# lipo-charger-station.net
KiCad netlist of a schematic drawn in EAGLE
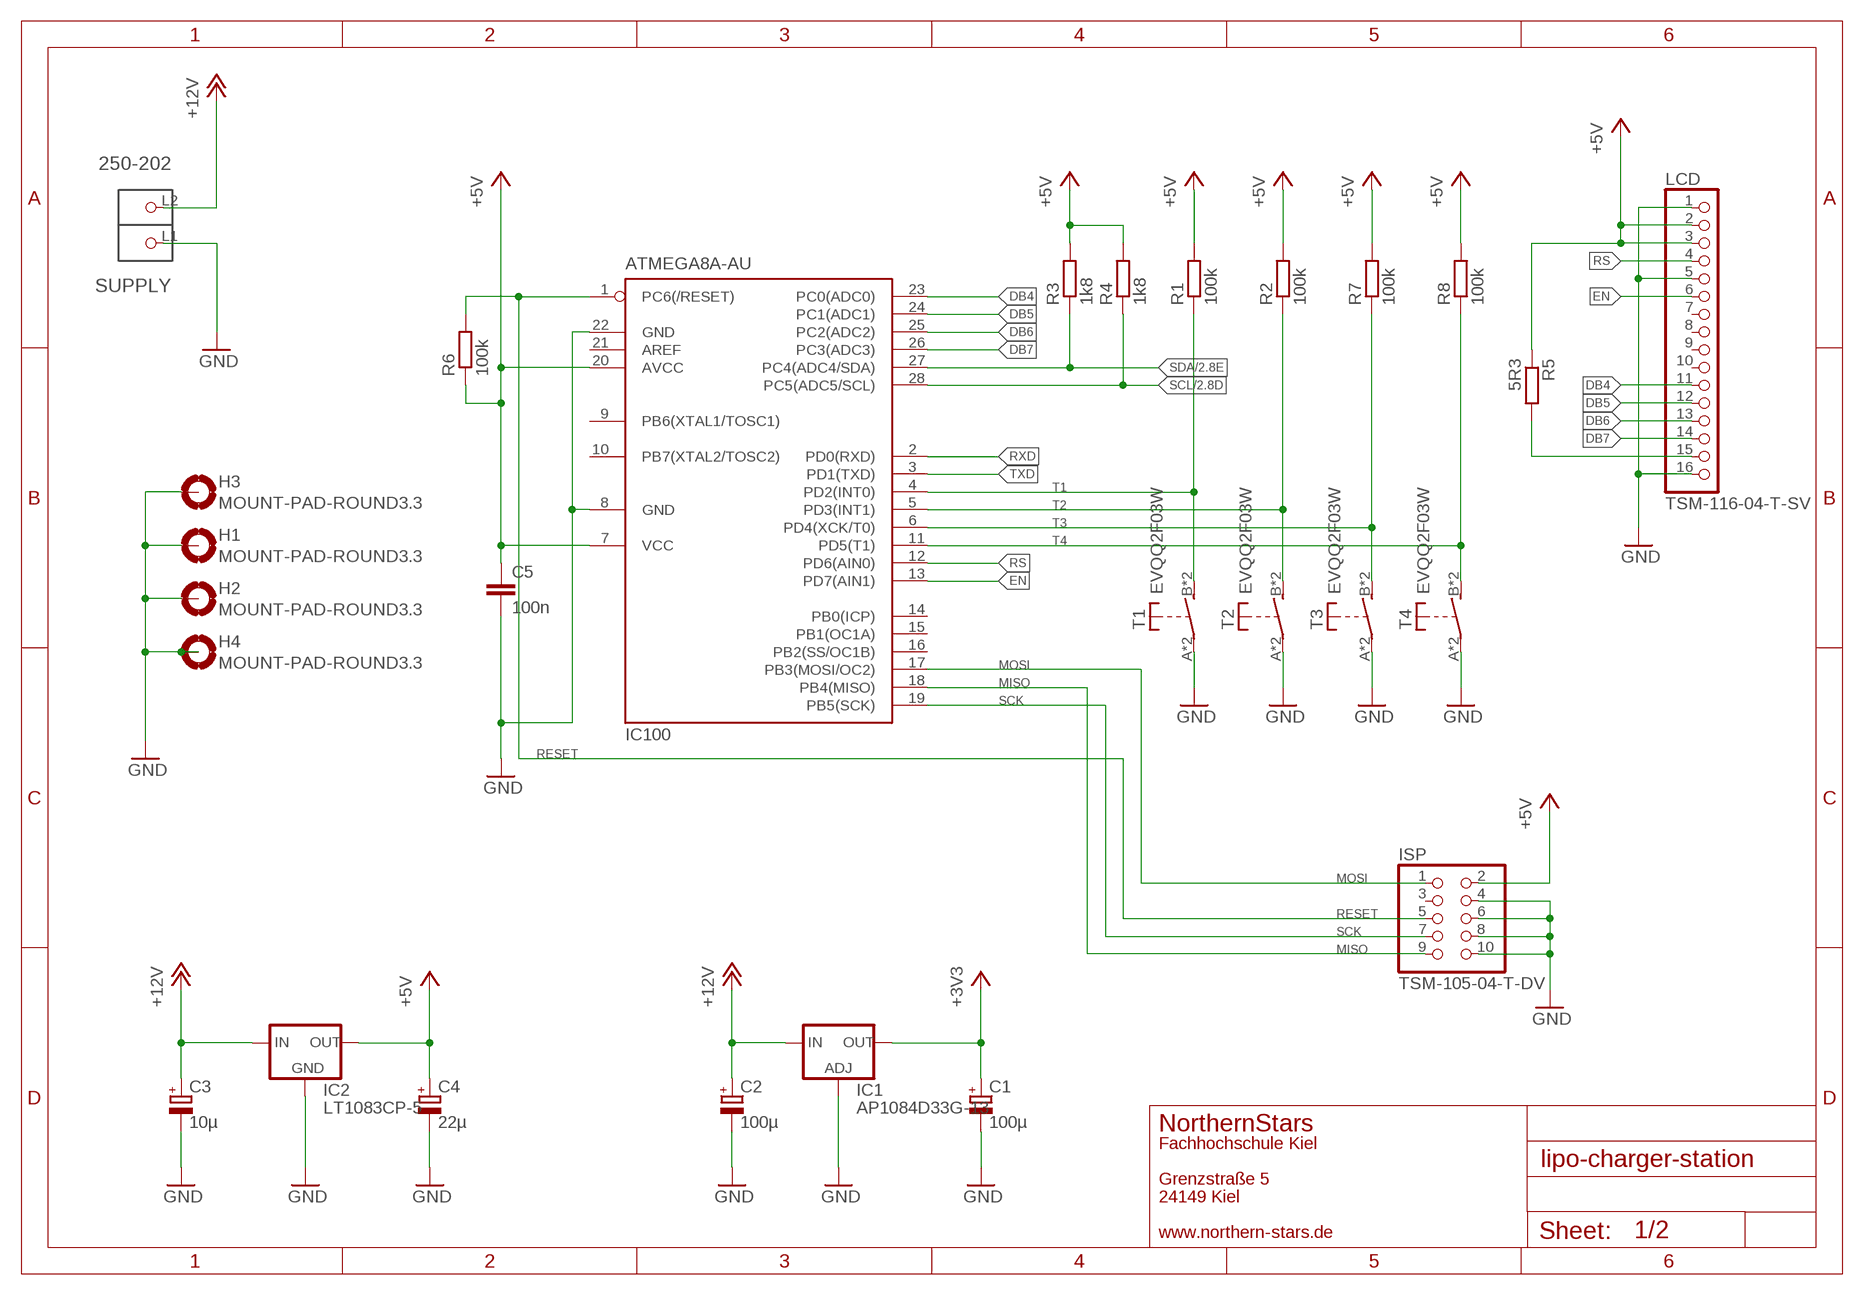
[diagram p0: schematic, sheet 1]
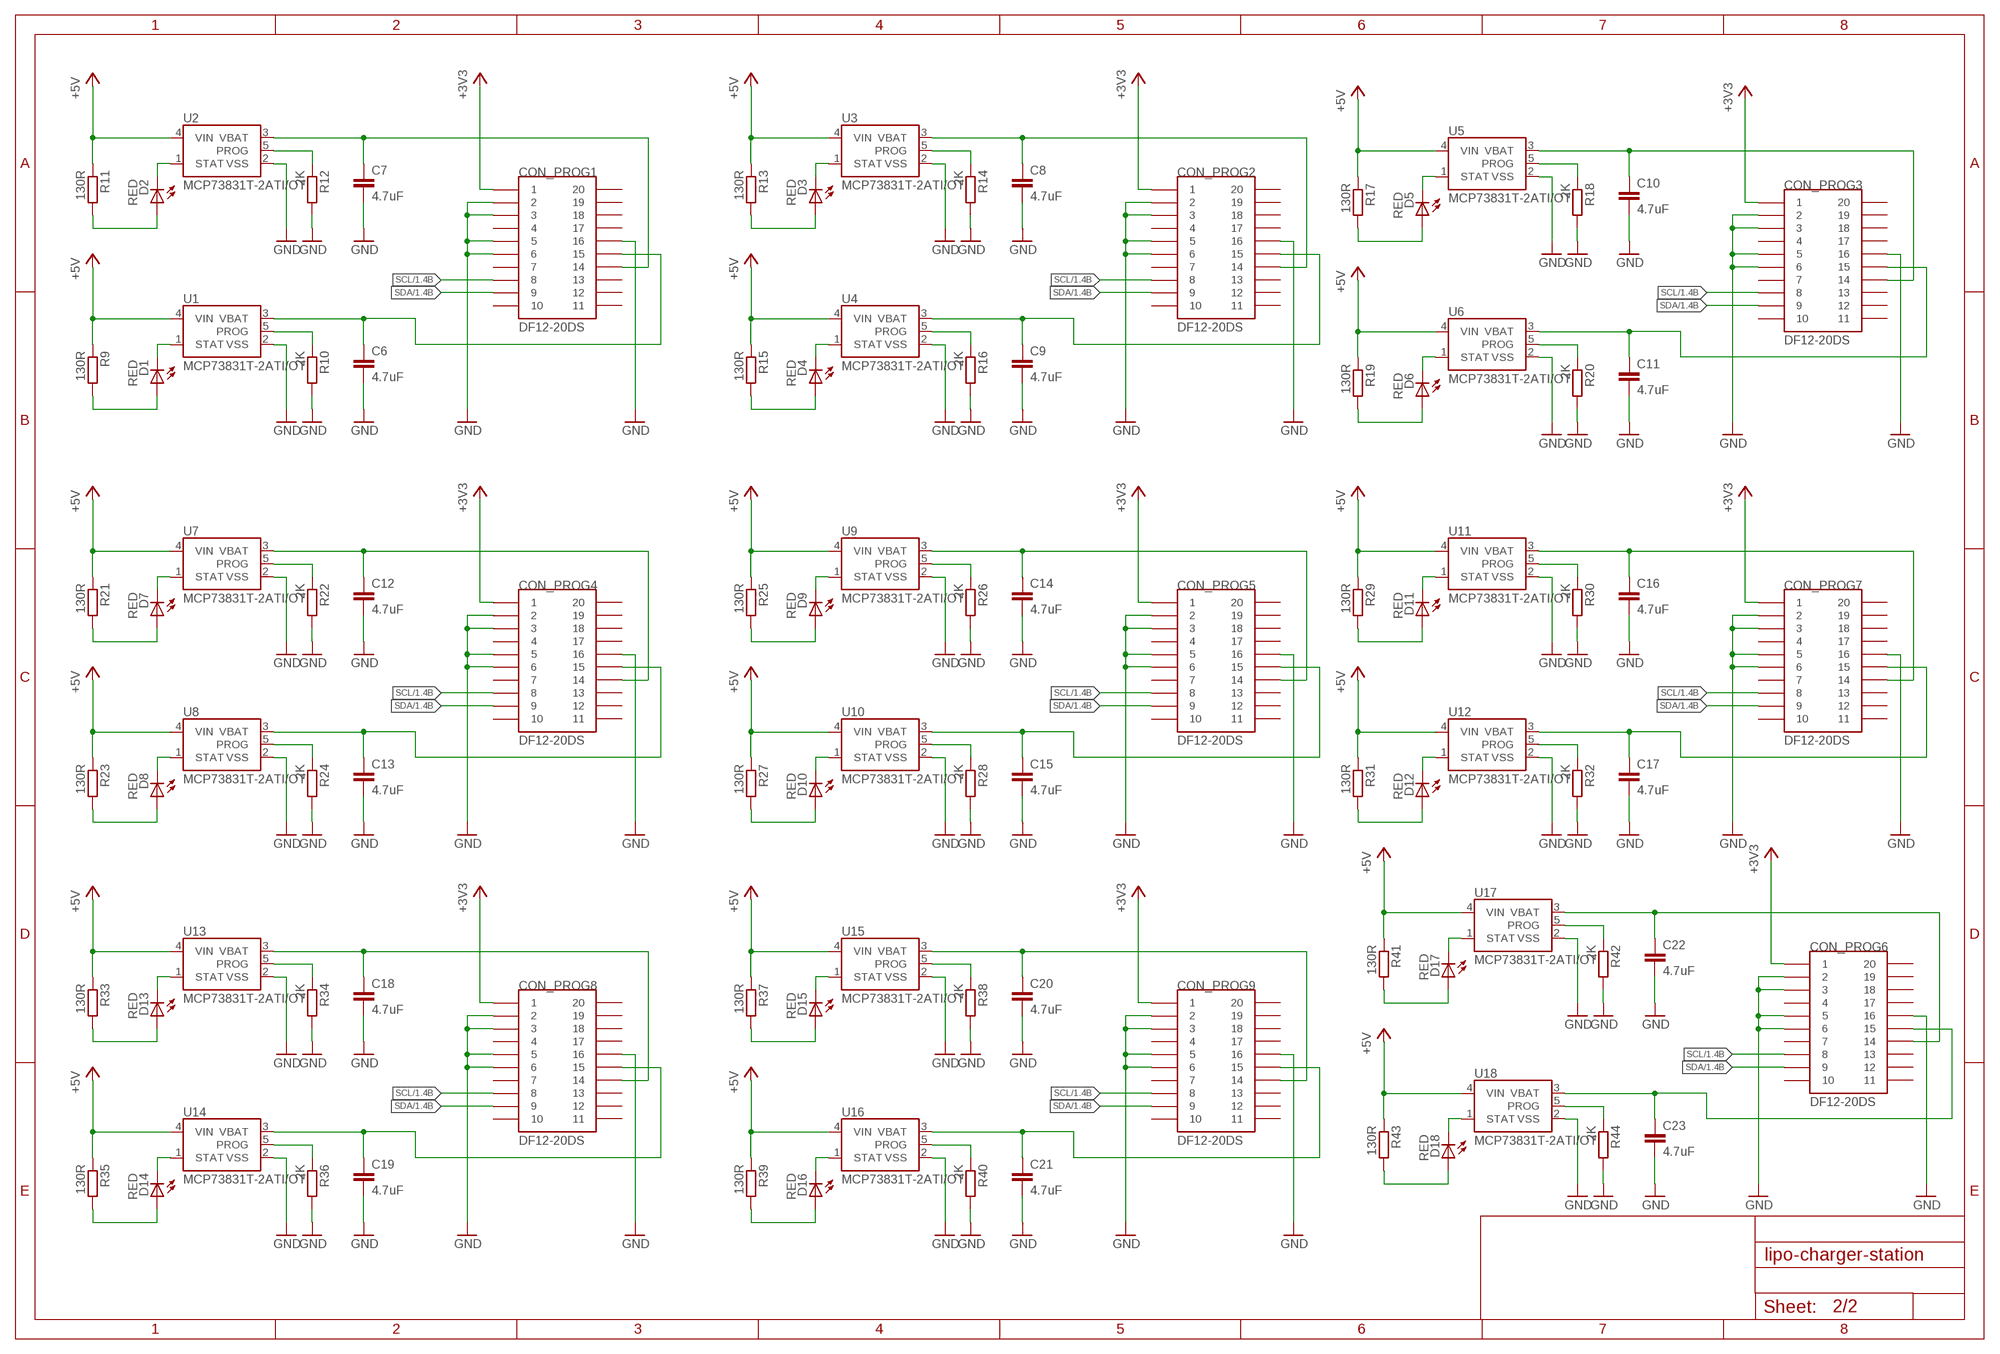
[diagram p1: schematic, sheet 2]

(export (version "E")
  (design (tool "Eeschema 10.0.6"))
  (components
    (comp (ref "C1")
      (value "100µ")
      (footprint "eagle-import:PANASONIC_G")
      (libsource (lib "eagle-import") (part "CPOL-EUG"))
    )
    (comp (ref "C2")
      (value "100µ")
      (footprint "eagle-import:PANASONIC_G")
      (libsource (lib "eagle-import") (part "CPOL-EUG"))
    )
    (comp (ref "C3")
      (value "10µ")
      (footprint "eagle-import:PANASONIC_D")
      (libsource (lib "eagle-import") (part "CPOL-EUD"))
    )
    (comp (ref "C4")
      (value "22µ")
      (footprint "eagle-import:PANASONIC_E")
      (libsource (lib "eagle-import") (part "CPOL-EUE"))
    )
    (comp (ref "C5")
      (value "100n")
      (footprint "eagle-import:C1206")
      (libsource (lib "eagle-import") (part "C-EUC1206"))
    )
    (comp (ref "H1")
      (value "MOUNT-PAD-ROUND3.3")
      (footprint "eagle-import:3,3-PAD")
      (libsource (lib "eagle-import") (part "MOUNT-PAD-ROUND3.3"))
    )
    (comp (ref "H2")
      (value "MOUNT-PAD-ROUND3.3")
      (footprint "eagle-import:3,3-PAD")
      (libsource (lib "eagle-import") (part "MOUNT-PAD-ROUND3.3"))
    )
    (comp (ref "H3")
      (value "MOUNT-PAD-ROUND3.3")
      (footprint "eagle-import:3,3-PAD")
      (libsource (lib "eagle-import") (part "MOUNT-PAD-ROUND3.3"))
    )
    (comp (ref "H4")
      (value "MOUNT-PAD-ROUND3.3")
      (footprint "eagle-import:3,3-PAD")
      (libsource (lib "eagle-import") (part "MOUNT-PAD-ROUND3.3"))
    )
    (comp (ref "IC1")
      (value "AP1084D33G-13")
      (footprint "eagle-import:TO252")
      (libsource (lib "eagle-import") (part "AP1084"))
    )
    (comp (ref "IC2")
      (value "LT1083CP-5")
      (footprint "eagle-import:TO3P")
      (libsource (lib "eagle-import") (part "LT108XCP"))
    )
    (comp (ref "IC100")
      (value "ATMEGA8A-AU")
      (footprint "eagle-import:DIL28-3")
      (libsource (lib "eagle-import") (part "MEGA8-P"))
    )
    (comp (ref "ISP")
      (value "TSM-105-04-T-DV")
      (footprint "eagle-import:2X05SMD")
      (libsource (lib "eagle-import") (part "PINHD-2X05_2.54-SMD"))
    )
    (comp (ref "LCD")
      (value "TSM-116-04-T-SV")
      (footprint "eagle-import:1X16SMD")
      (libsource (lib "eagle-import") (part "PINHD-1X16_2.54-SMD"))
    )
    (comp (ref "R1")
      (value "100k")
      (footprint "eagle-import:R1206")
      (libsource (lib "eagle-import") (part "R-EU_R1206"))
    )
    (comp (ref "R2")
      (value "100k")
      (footprint "eagle-import:R1206")
      (libsource (lib "eagle-import") (part "R-EU_R1206"))
    )
    (comp (ref "R3")
      (value "1k8")
      (footprint "eagle-import:R1206")
      (libsource (lib "eagle-import") (part "R-EU_R1206"))
    )
    (comp (ref "R4")
      (value "1k8")
      (footprint "eagle-import:R1206")
      (libsource (lib "eagle-import") (part "R-EU_R1206"))
    )
    (comp (ref "R5")
      (value "5R3")
      (footprint "eagle-import:R1206")
      (libsource (lib "eagle-import") (part "R-EU_R1206"))
    )
    (comp (ref "R6")
      (value "100k")
      (footprint "eagle-import:R1206")
      (libsource (lib "eagle-import") (part "R-EU_R1206"))
    )
    (comp (ref "R7")
      (value "100k")
      (footprint "eagle-import:R1206")
      (libsource (lib "eagle-import") (part "R-EU_R1206"))
    )
    (comp (ref "R8")
      (value "100k")
      (footprint "eagle-import:R1206")
      (libsource (lib "eagle-import") (part "R-EU_R1206"))
    )
    (comp (ref "SUPPLY")
      (value "250-202")
      (footprint "eagle-import:P-250-202")
      (libsource (lib "eagle-import") (part "250-202"))
    )
    (comp (ref "T1")
      (value "EVQQ2F03W")
      (footprint "eagle-import:SMD_TASTER_PANASONIC")
      (libsource (lib "eagle-import") (part "SMD_TASTER_PANASONIC"))
    )
    (comp (ref "T2")
      (value "EVQQ2F03W")
      (footprint "eagle-import:SMD_TASTER_PANASONIC")
      (fields (field (name "DEVICE") "EVQQ2F03W"))
      (libsource (lib "eagle-import") (part "SMD_TASTER_PANASONIC"))
    )
    (comp (ref "T3")
      (value "EVQQ2F03W")
      (footprint "eagle-import:SMD_TASTER_PANASONIC")
      (fields (field (name "DEVICE") "EVQQ2F03W"))
      (libsource (lib "eagle-import") (part "SMD_TASTER_PANASONIC"))
    )
    (comp (ref "T4")
      (value "EVQQ2F03W")
      (footprint "eagle-import:SMD_TASTER_PANASONIC")
      (fields (field (name "DEVICE") "EVQQ2F03W"))
      (libsource (lib "eagle-import") (part "SMD_TASTER_PANASONIC"))
    )
    (comp (ref "C6")
      (value "4.7uF")
      (footprint "eagle-import:C1206")
      (libsource (lib "eagle-import") (part "C-EUC1206"))
    )
    (comp (ref "C7")
      (value "4.7uF")
      (footprint "eagle-import:C1206")
      (libsource (lib "eagle-import") (part "C-EUC1206"))
    )
    (comp (ref "C8")
      (value "4.7uF")
      (footprint "eagle-import:C1206")
      (libsource (lib "eagle-import") (part "C-EUC1206"))
    )
    (comp (ref "C9")
      (value "4.7uF")
      (footprint "eagle-import:C1206")
      (libsource (lib "eagle-import") (part "C-EUC1206"))
    )
    (comp (ref "C10")
      (value "4.7uF")
      (footprint "eagle-import:C1206")
      (libsource (lib "eagle-import") (part "C-EUC1206"))
    )
    (comp (ref "C11")
      (value "4.7uF")
      (footprint "eagle-import:C1206")
      (libsource (lib "eagle-import") (part "C-EUC1206"))
    )
    (comp (ref "C12")
      (value "4.7uF")
      (footprint "eagle-import:C1206")
      (libsource (lib "eagle-import") (part "C-EUC1206"))
    )
    (comp (ref "C13")
      (value "4.7uF")
      (footprint "eagle-import:C1206")
      (libsource (lib "eagle-import") (part "C-EUC1206"))
    )
    (comp (ref "C14")
      (value "4.7uF")
      (footprint "eagle-import:C1206")
      (libsource (lib "eagle-import") (part "C-EUC1206"))
    )
    (comp (ref "C15")
      (value "4.7uF")
      (footprint "eagle-import:C1206")
      (libsource (lib "eagle-import") (part "C-EUC1206"))
    )
    (comp (ref "C16")
      (value "4.7uF")
      (footprint "eagle-import:C1206")
      (libsource (lib "eagle-import") (part "C-EUC1206"))
    )
    (comp (ref "C17")
      (value "4.7uF")
      (footprint "eagle-import:C1206")
      (libsource (lib "eagle-import") (part "C-EUC1206"))
    )
    (comp (ref "C18")
      (value "4.7uF")
      (footprint "eagle-import:C1206")
      (libsource (lib "eagle-import") (part "C-EUC1206"))
    )
    (comp (ref "C19")
      (value "4.7uF")
      (footprint "eagle-import:C1206")
      (libsource (lib "eagle-import") (part "C-EUC1206"))
    )
    (comp (ref "C20")
      (value "4.7uF")
      (footprint "eagle-import:C1206")
      (libsource (lib "eagle-import") (part "C-EUC1206"))
    )
    (comp (ref "C21")
      (value "4.7uF")
      (footprint "eagle-import:C1206")
      (libsource (lib "eagle-import") (part "C-EUC1206"))
    )
    (comp (ref "C22")
      (value "4.7uF")
      (footprint "eagle-import:C1206")
      (libsource (lib "eagle-import") (part "C-EUC1206"))
    )
    (comp (ref "C23")
      (value "4.7uF")
      (footprint "eagle-import:C1206")
      (libsource (lib "eagle-import") (part "C-EUC1206"))
    )
    (comp (ref "CON_PROG1")
      (value "DF12-20DS")
      (footprint "eagle-import:DF12-20DS")
      (libsource (lib "eagle-import") (part "DF12-20DS"))
    )
    (comp (ref "CON_PROG2")
      (value "DF12-20DS")
      (footprint "eagle-import:DF12-20DS")
      (libsource (lib "eagle-import") (part "DF12-20DS"))
    )
    (comp (ref "CON_PROG3")
      (value "DF12-20DS")
      (footprint "eagle-import:DF12-20DS")
      (libsource (lib "eagle-import") (part "DF12-20DS"))
    )
    (comp (ref "CON_PROG4")
      (value "DF12-20DS")
      (footprint "eagle-import:DF12-20DS")
      (libsource (lib "eagle-import") (part "DF12-20DS"))
    )
    (comp (ref "CON_PROG5")
      (value "DF12-20DS")
      (footprint "eagle-import:DF12-20DS")
      (libsource (lib "eagle-import") (part "DF12-20DS"))
    )
    (comp (ref "CON_PROG6")
      (value "DF12-20DS")
      (footprint "eagle-import:DF12-20DS")
      (libsource (lib "eagle-import") (part "DF12-20DS"))
    )
    (comp (ref "CON_PROG7")
      (value "DF12-20DS")
      (footprint "eagle-import:DF12-20DS")
      (libsource (lib "eagle-import") (part "DF12-20DS"))
    )
    (comp (ref "CON_PROG8")
      (value "DF12-20DS")
      (footprint "eagle-import:DF12-20DS")
      (libsource (lib "eagle-import") (part "DF12-20DS"))
    )
    (comp (ref "CON_PROG9")
      (value "DF12-20DS")
      (footprint "eagle-import:DF12-20DS")
      (libsource (lib "eagle-import") (part "DF12-20DS"))
    )
    (comp (ref "D1")
      (value "RED")
      (footprint "eagle-import:CHIPLED_1206")
      (libsource (lib "eagle-import") (part "LEDCHIPLED_1206"))
    )
    (comp (ref "D2")
      (value "RED")
      (footprint "eagle-import:CHIPLED_1206")
      (libsource (lib "eagle-import") (part "LEDCHIPLED_1206"))
    )
    (comp (ref "D3")
      (value "RED")
      (footprint "eagle-import:CHIPLED_1206")
      (libsource (lib "eagle-import") (part "LEDCHIPLED_1206"))
    )
    (comp (ref "D4")
      (value "RED")
      (footprint "eagle-import:CHIPLED_1206")
      (libsource (lib "eagle-import") (part "LEDCHIPLED_1206"))
    )
    (comp (ref "D5")
      (value "RED")
      (footprint "eagle-import:CHIPLED_1206")
      (libsource (lib "eagle-import") (part "LEDCHIPLED_1206"))
    )
    (comp (ref "D6")
      (value "RED")
      (footprint "eagle-import:CHIPLED_1206")
      (libsource (lib "eagle-import") (part "LEDCHIPLED_1206"))
    )
    (comp (ref "D7")
      (value "RED")
      (footprint "eagle-import:CHIPLED_1206")
      (libsource (lib "eagle-import") (part "LEDCHIPLED_1206"))
    )
    (comp (ref "D8")
      (value "RED")
      (footprint "eagle-import:CHIPLED_1206")
      (libsource (lib "eagle-import") (part "LEDCHIPLED_1206"))
    )
    (comp (ref "D9")
      (value "RED")
      (footprint "eagle-import:CHIPLED_1206")
      (libsource (lib "eagle-import") (part "LEDCHIPLED_1206"))
    )
    (comp (ref "D10")
      (value "RED")
      (footprint "eagle-import:CHIPLED_1206")
      (libsource (lib "eagle-import") (part "LEDCHIPLED_1206"))
    )
    (comp (ref "D11")
      (value "RED")
      (footprint "eagle-import:CHIPLED_1206")
      (libsource (lib "eagle-import") (part "LEDCHIPLED_1206"))
    )
    (comp (ref "D12")
      (value "RED")
      (footprint "eagle-import:CHIPLED_1206")
      (libsource (lib "eagle-import") (part "LEDCHIPLED_1206"))
    )
    (comp (ref "D13")
      (value "RED")
      (footprint "eagle-import:CHIPLED_1206")
      (libsource (lib "eagle-import") (part "LEDCHIPLED_1206"))
    )
    (comp (ref "D14")
      (value "RED")
      (footprint "eagle-import:CHIPLED_1206")
      (libsource (lib "eagle-import") (part "LEDCHIPLED_1206"))
    )
    (comp (ref "D15")
      (value "RED")
      (footprint "eagle-import:CHIPLED_1206")
      (libsource (lib "eagle-import") (part "LEDCHIPLED_1206"))
    )
    (comp (ref "D16")
      (value "RED")
      (footprint "eagle-import:CHIPLED_1206")
      (libsource (lib "eagle-import") (part "LEDCHIPLED_1206"))
    )
    (comp (ref "D17")
      (value "RED")
      (footprint "eagle-import:CHIPLED_1206")
      (libsource (lib "eagle-import") (part "LEDCHIPLED_1206"))
    )
    (comp (ref "D18")
      (value "RED")
      (footprint "eagle-import:CHIPLED_1206")
      (libsource (lib "eagle-import") (part "LEDCHIPLED_1206"))
    )
    (comp (ref "R9")
      (value "130R")
      (footprint "eagle-import:R1206")
      (libsource (lib "eagle-import") (part "R-EU_R1206"))
    )
    (comp (ref "R10")
      (value "2K")
      (footprint "eagle-import:R1206")
      (libsource (lib "eagle-import") (part "R-EU_R1206"))
    )
    (comp (ref "R11")
      (value "130R")
      (footprint "eagle-import:R1206")
      (libsource (lib "eagle-import") (part "R-EU_R1206"))
    )
    (comp (ref "R12")
      (value "2K")
      (footprint "eagle-import:R1206")
      (libsource (lib "eagle-import") (part "R-EU_R1206"))
    )
    (comp (ref "R13")
      (value "130R")
      (footprint "eagle-import:R1206")
      (libsource (lib "eagle-import") (part "R-EU_R1206"))
    )
    (comp (ref "R14")
      (value "2K")
      (footprint "eagle-import:R1206")
      (libsource (lib "eagle-import") (part "R-EU_R1206"))
    )
    (comp (ref "R15")
      (value "130R")
      (footprint "eagle-import:R1206")
      (libsource (lib "eagle-import") (part "R-EU_R1206"))
    )
    (comp (ref "R16")
      (value "2K")
      (footprint "eagle-import:R1206")
      (libsource (lib "eagle-import") (part "R-EU_R1206"))
    )
    (comp (ref "R17")
      (value "130R")
      (footprint "eagle-import:R1206")
      (libsource (lib "eagle-import") (part "R-EU_R1206"))
    )
    (comp (ref "R18")
      (value "2K")
      (footprint "eagle-import:R1206")
      (libsource (lib "eagle-import") (part "R-EU_R1206"))
    )
    (comp (ref "R19")
      (value "130R")
      (footprint "eagle-import:R1206")
      (libsource (lib "eagle-import") (part "R-EU_R1206"))
    )
    (comp (ref "R20")
      (value "2K")
      (footprint "eagle-import:R1206")
      (libsource (lib "eagle-import") (part "R-EU_R1206"))
    )
    (comp (ref "R21")
      (value "130R")
      (footprint "eagle-import:R1206")
      (libsource (lib "eagle-import") (part "R-EU_R1206"))
    )
    (comp (ref "R22")
      (value "2K")
      (footprint "eagle-import:R1206")
      (libsource (lib "eagle-import") (part "R-EU_R1206"))
    )
    (comp (ref "R23")
      (value "130R")
      (footprint "eagle-import:R1206")
      (libsource (lib "eagle-import") (part "R-EU_R1206"))
    )
    (comp (ref "R24")
      (value "2K")
      (footprint "eagle-import:R1206")
      (libsource (lib "eagle-import") (part "R-EU_R1206"))
    )
    (comp (ref "R25")
      (value "130R")
      (footprint "eagle-import:R1206")
      (libsource (lib "eagle-import") (part "R-EU_R1206"))
    )
    (comp (ref "R26")
      (value "2K")
      (footprint "eagle-import:R1206")
      (libsource (lib "eagle-import") (part "R-EU_R1206"))
    )
    (comp (ref "R27")
      (value "130R")
      (footprint "eagle-import:R1206")
      (libsource (lib "eagle-import") (part "R-EU_R1206"))
    )
    (comp (ref "R28")
      (value "2K")
      (footprint "eagle-import:R1206")
      (libsource (lib "eagle-import") (part "R-EU_R1206"))
    )
    (comp (ref "R29")
      (value "130R")
      (footprint "eagle-import:R1206")
      (libsource (lib "eagle-import") (part "R-EU_R1206"))
    )
    (comp (ref "R30")
      (value "2K")
      (footprint "eagle-import:R1206")
      (libsource (lib "eagle-import") (part "R-EU_R1206"))
    )
    (comp (ref "R31")
      (value "130R")
      (footprint "eagle-import:R1206")
      (libsource (lib "eagle-import") (part "R-EU_R1206"))
    )
    (comp (ref "R32")
      (value "2K")
      (footprint "eagle-import:R1206")
      (libsource (lib "eagle-import") (part "R-EU_R1206"))
    )
    (comp (ref "R33")
      (value "130R")
      (footprint "eagle-import:R1206")
      (libsource (lib "eagle-import") (part "R-EU_R1206"))
    )
    (comp (ref "R34")
      (value "2K")
      (footprint "eagle-import:R1206")
      (libsource (lib "eagle-import") (part "R-EU_R1206"))
    )
    (comp (ref "R35")
      (value "130R")
      (footprint "eagle-import:R1206")
      (libsource (lib "eagle-import") (part "R-EU_R1206"))
    )
    (comp (ref "R36")
      (value "2K")
      (footprint "eagle-import:R1206")
      (libsource (lib "eagle-import") (part "R-EU_R1206"))
    )
    (comp (ref "R37")
      (value "130R")
      (footprint "eagle-import:R1206")
      (libsource (lib "eagle-import") (part "R-EU_R1206"))
    )
    (comp (ref "R38")
      (value "2K")
      (footprint "eagle-import:R1206")
      (libsource (lib "eagle-import") (part "R-EU_R1206"))
    )
    (comp (ref "R39")
      (value "130R")
      (footprint "eagle-import:R1206")
      (libsource (lib "eagle-import") (part "R-EU_R1206"))
    )
    (comp (ref "R40")
      (value "2K")
      (footprint "eagle-import:R1206")
      (libsource (lib "eagle-import") (part "R-EU_R1206"))
    )
    (comp (ref "R41")
      (value "130R")
      (footprint "eagle-import:R1206")
      (libsource (lib "eagle-import") (part "R-EU_R1206"))
    )
    (comp (ref "R42")
      (value "2K")
      (footprint "eagle-import:R1206")
      (libsource (lib "eagle-import") (part "R-EU_R1206"))
    )
    (comp (ref "R43")
      (value "130R")
      (footprint "eagle-import:R1206")
      (libsource (lib "eagle-import") (part "R-EU_R1206"))
    )
    (comp (ref "R44")
      (value "2K")
      (footprint "eagle-import:R1206")
      (libsource (lib "eagle-import") (part "R-EU_R1206"))
    )
    (comp (ref "U1")
      (value "MCP73831T-2ATI/OT")
      (footprint "eagle-import:SOT23-5")
      (libsource (lib "eagle-import") (part "MCP73831"))
    )
    (comp (ref "U2")
      (value "MCP73831T-2ATI/OT")
      (footprint "eagle-import:SOT23-5")
      (libsource (lib "eagle-import") (part "MCP73831"))
    )
    (comp (ref "U3")
      (value "MCP73831T-2ATI/OT")
      (footprint "eagle-import:SOT23-5")
      (libsource (lib "eagle-import") (part "MCP73831"))
    )
    (comp (ref "U4")
      (value "MCP73831T-2ATI/OT")
      (footprint "eagle-import:SOT23-5")
      (libsource (lib "eagle-import") (part "MCP73831"))
    )
    (comp (ref "U5")
      (value "MCP73831T-2ATI/OT")
      (footprint "eagle-import:SOT23-5")
      (libsource (lib "eagle-import") (part "MCP73831"))
    )
    (comp (ref "U6")
      (value "MCP73831T-2ATI/OT")
      (footprint "eagle-import:SOT23-5")
      (libsource (lib "eagle-import") (part "MCP73831"))
    )
    (comp (ref "U7")
      (value "MCP73831T-2ATI/OT")
      (footprint "eagle-import:SOT23-5")
      (libsource (lib "eagle-import") (part "MCP73831"))
    )
    (comp (ref "U8")
      (value "MCP73831T-2ATI/OT")
      (footprint "eagle-import:SOT23-5")
      (libsource (lib "eagle-import") (part "MCP73831"))
    )
    (comp (ref "U9")
      (value "MCP73831T-2ATI/OT")
      (footprint "eagle-import:SOT23-5")
      (libsource (lib "eagle-import") (part "MCP73831"))
    )
    (comp (ref "U10")
      (value "MCP73831T-2ATI/OT")
      (footprint "eagle-import:SOT23-5")
      (libsource (lib "eagle-import") (part "MCP73831"))
    )
    (comp (ref "U11")
      (value "MCP73831T-2ATI/OT")
      (footprint "eagle-import:SOT23-5")
      (libsource (lib "eagle-import") (part "MCP73831"))
    )
    (comp (ref "U12")
      (value "MCP73831T-2ATI/OT")
      (footprint "eagle-import:SOT23-5")
      (libsource (lib "eagle-import") (part "MCP73831"))
    )
    (comp (ref "U13")
      (value "MCP73831T-2ATI/OT")
      (footprint "eagle-import:SOT23-5")
      (libsource (lib "eagle-import") (part "MCP73831"))
    )
    (comp (ref "U14")
      (value "MCP73831T-2ATI/OT")
      (footprint "eagle-import:SOT23-5")
      (libsource (lib "eagle-import") (part "MCP73831"))
    )
    (comp (ref "U15")
      (value "MCP73831T-2ATI/OT")
      (footprint "eagle-import:SOT23-5")
      (libsource (lib "eagle-import") (part "MCP73831"))
    )
    (comp (ref "U16")
      (value "MCP73831T-2ATI/OT")
      (footprint "eagle-import:SOT23-5")
      (libsource (lib "eagle-import") (part "MCP73831"))
    )
    (comp (ref "U17")
      (value "MCP73831T-2ATI/OT")
      (footprint "eagle-import:SOT23-5")
      (libsource (lib "eagle-import") (part "MCP73831"))
    )
    (comp (ref "U18")
      (value "MCP73831T-2ATI/OT")
      (footprint "eagle-import:SOT23-5")
      (libsource (lib "eagle-import") (part "MCP73831"))
    )
  )
  (nets
    (net (code "1") (name "+3V3") (class "Default")
      (node (ref "C1") (pin "+") (pinfunction "+_+") (pintype "passive"))
      (node (ref "CON_PROG1") (pin "1") (pinfunction "1_1") (pintype "bidirectional"))
      (node (ref "CON_PROG2") (pin "1") (pinfunction "1_1") (pintype "bidirectional"))
      (node (ref "CON_PROG3") (pin "1") (pinfunction "1_1") (pintype "bidirectional"))
      (node (ref "CON_PROG4") (pin "1") (pinfunction "1_1") (pintype "bidirectional"))
      (node (ref "CON_PROG5") (pin "1") (pinfunction "1_1") (pintype "bidirectional"))
      (node (ref "CON_PROG6") (pin "1") (pinfunction "1_1") (pintype "bidirectional"))
      (node (ref "CON_PROG7") (pin "1") (pinfunction "1_1") (pintype "bidirectional"))
      (node (ref "CON_PROG8") (pin "1") (pinfunction "1_1") (pintype "bidirectional"))
      (node (ref "CON_PROG9") (pin "1") (pinfunction "1_1") (pintype "bidirectional"))
      (node (ref "IC1") (pin "3") (pinfunction "OUT_3") (pintype "passive"))
    )
    (net (code "2") (name "+5V") (class "Default")
      (node (ref "C4") (pin "+") (pinfunction "+_+") (pintype "passive"))
      (node (ref "C5") (pin "1") (pinfunction "1_1") (pintype "passive"))
      (node (ref "IC100") (pin "20") (pinfunction "AVCC_20") (pintype "power_in"))
      (node (ref "IC100") (pin "7") (pinfunction "VCC_7") (pintype "power_in"))
      (node (ref "IC2") (pin "2") (pinfunction "OUT_2") (pintype "passive"))
      (node (ref "ISP") (pin "2") (pinfunction "2_2") (pintype "passive"))
      (node (ref "LCD") (pin "2") (pinfunction "2_2") (pintype "passive"))
      (node (ref "LCD") (pin "3") (pinfunction "3_3") (pintype "passive"))
      (node (ref "R1") (pin "2") (pinfunction "2_2") (pintype "passive"))
      (node (ref "R11") (pin "1") (pinfunction "1_1") (pintype "passive"))
      (node (ref "R13") (pin "1") (pinfunction "1_1") (pintype "passive"))
      (node (ref "R15") (pin "1") (pinfunction "1_1") (pintype "passive"))
      (node (ref "R17") (pin "1") (pinfunction "1_1") (pintype "passive"))
      (node (ref "R19") (pin "1") (pinfunction "1_1") (pintype "passive"))
      (node (ref "R2") (pin "2") (pinfunction "2_2") (pintype "passive"))
      (node (ref "R21") (pin "1") (pinfunction "1_1") (pintype "passive"))
      (node (ref "R23") (pin "1") (pinfunction "1_1") (pintype "passive"))
      (node (ref "R25") (pin "1") (pinfunction "1_1") (pintype "passive"))
      (node (ref "R27") (pin "1") (pinfunction "1_1") (pintype "passive"))
      (node (ref "R29") (pin "1") (pinfunction "1_1") (pintype "passive"))
      (node (ref "R3") (pin "2") (pinfunction "2_2") (pintype "passive"))
      (node (ref "R31") (pin "1") (pinfunction "1_1") (pintype "passive"))
      (node (ref "R33") (pin "1") (pinfunction "1_1") (pintype "passive"))
      (node (ref "R35") (pin "1") (pinfunction "1_1") (pintype "passive"))
      (node (ref "R37") (pin "1") (pinfunction "1_1") (pintype "passive"))
      (node (ref "R39") (pin "1") (pinfunction "1_1") (pintype "passive"))
      (node (ref "R4") (pin "2") (pinfunction "2_2") (pintype "passive"))
      (node (ref "R41") (pin "1") (pinfunction "1_1") (pintype "passive"))
      (node (ref "R43") (pin "1") (pinfunction "1_1") (pintype "passive"))
      (node (ref "R5") (pin "1") (pinfunction "1_1") (pintype "passive"))
      (node (ref "R6") (pin "1") (pinfunction "1_1") (pintype "passive"))
      (node (ref "R7") (pin "2") (pinfunction "2_2") (pintype "passive"))
      (node (ref "R8") (pin "2") (pinfunction "2_2") (pintype "passive"))
      (node (ref "R9") (pin "1") (pinfunction "1_1") (pintype "passive"))
      (node (ref "U1") (pin "4") (pinfunction "VIN_4") (pintype "power_in"))
      (node (ref "U10") (pin "4") (pinfunction "VIN_4") (pintype "power_in"))
      (node (ref "U11") (pin "4") (pinfunction "VIN_4") (pintype "power_in"))
      (node (ref "U12") (pin "4") (pinfunction "VIN_4") (pintype "power_in"))
      (node (ref "U13") (pin "4") (pinfunction "VIN_4") (pintype "power_in"))
      (node (ref "U14") (pin "4") (pinfunction "VIN_4") (pintype "power_in"))
      (node (ref "U15") (pin "4") (pinfunction "VIN_4") (pintype "power_in"))
      (node (ref "U16") (pin "4") (pinfunction "VIN_4") (pintype "power_in"))
      (node (ref "U17") (pin "4") (pinfunction "VIN_4") (pintype "power_in"))
      (node (ref "U18") (pin "4") (pinfunction "VIN_4") (pintype "power_in"))
      (node (ref "U2") (pin "4") (pinfunction "VIN_4") (pintype "power_in"))
      (node (ref "U3") (pin "4") (pinfunction "VIN_4") (pintype "power_in"))
      (node (ref "U4") (pin "4") (pinfunction "VIN_4") (pintype "power_in"))
      (node (ref "U5") (pin "4") (pinfunction "VIN_4") (pintype "power_in"))
      (node (ref "U6") (pin "4") (pinfunction "VIN_4") (pintype "power_in"))
      (node (ref "U7") (pin "4") (pinfunction "VIN_4") (pintype "power_in"))
      (node (ref "U8") (pin "4") (pinfunction "VIN_4") (pintype "power_in"))
      (node (ref "U9") (pin "4") (pinfunction "VIN_4") (pintype "power_in"))
    )
    (net (code "3") (name "+12V") (class "Default")
      (node (ref "C2") (pin "+") (pinfunction "+_+") (pintype "passive"))
      (node (ref "C3") (pin "+") (pinfunction "+_+") (pintype "passive"))
      (node (ref "IC1") (pin "2") (pinfunction "IN_2") (pintype "input"))
      (node (ref "IC2") (pin "3") (pinfunction "IN_3") (pintype "input"))
      (node (ref "SUPPLY") (pin "L2") (pinfunction "P2_L2") (pintype "bidirectional"))
    )
    (net (code "4") (name "DB4") (class "Default")
      (node (ref "IC100") (pin "23") (pinfunction "PC0(ADC0)_23") (pintype "bidirectional"))
      (node (ref "LCD") (pin "11") (pinfunction "11_11") (pintype "passive"))
    )
    (net (code "5") (name "DB5") (class "Default")
      (node (ref "IC100") (pin "24") (pinfunction "PC1(ADC1)_24") (pintype "bidirectional"))
      (node (ref "LCD") (pin "12") (pinfunction "12_12") (pintype "passive"))
    )
    (net (code "6") (name "DB6") (class "Default")
      (node (ref "IC100") (pin "25") (pinfunction "PC2(ADC2)_25") (pintype "bidirectional"))
      (node (ref "LCD") (pin "13") (pinfunction "13_13") (pintype "passive"))
    )
    (net (code "7") (name "DB7") (class "Default")
      (node (ref "IC100") (pin "26") (pinfunction "PC3(ADC3)_26") (pintype "bidirectional"))
      (node (ref "LCD") (pin "14") (pinfunction "14_14") (pintype "passive"))
    )
    (net (code "8") (name "EN") (class "Default")
      (node (ref "IC100") (pin "13") (pinfunction "PD7(AIN1)_13") (pintype "bidirectional"))
      (node (ref "LCD") (pin "6") (pinfunction "6_6") (pintype "passive"))
    )
    (net (code "9") (name "GND") (class "Default")
      (node (ref "C1") (pin "-") (pinfunction "-_-") (pintype "passive"))
      (node (ref "C10") (pin "2") (pinfunction "2_2") (pintype "passive"))
      (node (ref "C11") (pin "2") (pinfunction "2_2") (pintype "passive"))
      (node (ref "C12") (pin "2") (pinfunction "2_2") (pintype "passive"))
      (node (ref "C13") (pin "2") (pinfunction "2_2") (pintype "passive"))
      (node (ref "C14") (pin "2") (pinfunction "2_2") (pintype "passive"))
      (node (ref "C15") (pin "2") (pinfunction "2_2") (pintype "passive"))
      (node (ref "C16") (pin "2") (pinfunction "2_2") (pintype "passive"))
      (node (ref "C17") (pin "2") (pinfunction "2_2") (pintype "passive"))
      (node (ref "C18") (pin "2") (pinfunction "2_2") (pintype "passive"))
      (node (ref "C19") (pin "2") (pinfunction "2_2") (pintype "passive"))
      (node (ref "C2") (pin "-") (pinfunction "-_-") (pintype "passive"))
      (node (ref "C20") (pin "2") (pinfunction "2_2") (pintype "passive"))
      (node (ref "C21") (pin "2") (pinfunction "2_2") (pintype "passive"))
      (node (ref "C22") (pin "2") (pinfunction "2_2") (pintype "passive"))
      (node (ref "C23") (pin "2") (pinfunction "2_2") (pintype "passive"))
      (node (ref "C3") (pin "-") (pinfunction "-_-") (pintype "passive"))
      (node (ref "C4") (pin "-") (pinfunction "-_-") (pintype "passive"))
      (node (ref "C5") (pin "2") (pinfunction "2_2") (pintype "passive"))
      (node (ref "C6") (pin "2") (pinfunction "2_2") (pintype "passive"))
      (node (ref "C7") (pin "2") (pinfunction "2_2") (pintype "passive"))
      (node (ref "C8") (pin "2") (pinfunction "2_2") (pintype "passive"))
      (node (ref "C9") (pin "2") (pinfunction "2_2") (pintype "passive"))
      (node (ref "CON_PROG1") (pin "16") (pinfunction "16_16") (pintype "bidirectional"))
      (node (ref "CON_PROG1") (pin "2") (pinfunction "2_2") (pintype "bidirectional"))
      (node (ref "CON_PROG1") (pin "3") (pinfunction "3_3") (pintype "bidirectional"))
      (node (ref "CON_PROG1") (pin "5") (pinfunction "5_5") (pintype "bidirectional"))
      (node (ref "CON_PROG1") (pin "6") (pinfunction "6_6") (pintype "bidirectional"))
      (node (ref "CON_PROG2") (pin "16") (pinfunction "16_16") (pintype "bidirectional"))
      (node (ref "CON_PROG2") (pin "2") (pinfunction "2_2") (pintype "bidirectional"))
      (node (ref "CON_PROG2") (pin "3") (pinfunction "3_3") (pintype "bidirectional"))
      (node (ref "CON_PROG2") (pin "5") (pinfunction "5_5") (pintype "bidirectional"))
      (node (ref "CON_PROG2") (pin "6") (pinfunction "6_6") (pintype "bidirectional"))
      (node (ref "CON_PROG3") (pin "16") (pinfunction "16_16") (pintype "bidirectional"))
      (node (ref "CON_PROG3") (pin "2") (pinfunction "2_2") (pintype "bidirectional"))
      (node (ref "CON_PROG3") (pin "3") (pinfunction "3_3") (pintype "bidirectional"))
      (node (ref "CON_PROG3") (pin "5") (pinfunction "5_5") (pintype "bidirectional"))
      (node (ref "CON_PROG3") (pin "6") (pinfunction "6_6") (pintype "bidirectional"))
      (node (ref "CON_PROG4") (pin "16") (pinfunction "16_16") (pintype "bidirectional"))
      (node (ref "CON_PROG4") (pin "2") (pinfunction "2_2") (pintype "bidirectional"))
      (node (ref "CON_PROG4") (pin "3") (pinfunction "3_3") (pintype "bidirectional"))
      (node (ref "CON_PROG4") (pin "5") (pinfunction "5_5") (pintype "bidirectional"))
      (node (ref "CON_PROG4") (pin "6") (pinfunction "6_6") (pintype "bidirectional"))
      (node (ref "CON_PROG5") (pin "16") (pinfunction "16_16") (pintype "bidirectional"))
      (node (ref "CON_PROG5") (pin "2") (pinfunction "2_2") (pintype "bidirectional"))
      (node (ref "CON_PROG5") (pin "3") (pinfunction "3_3") (pintype "bidirectional"))
      (node (ref "CON_PROG5") (pin "5") (pinfunction "5_5") (pintype "bidirectional"))
      (node (ref "CON_PROG5") (pin "6") (pinfunction "6_6") (pintype "bidirectional"))
      (node (ref "CON_PROG6") (pin "16") (pinfunction "16_16") (pintype "bidirectional"))
      (node (ref "CON_PROG6") (pin "2") (pinfunction "2_2") (pintype "bidirectional"))
      (node (ref "CON_PROG6") (pin "3") (pinfunction "3_3") (pintype "bidirectional"))
      (node (ref "CON_PROG6") (pin "5") (pinfunction "5_5") (pintype "bidirectional"))
      (node (ref "CON_PROG6") (pin "6") (pinfunction "6_6") (pintype "bidirectional"))
      (node (ref "CON_PROG7") (pin "16") (pinfunction "16_16") (pintype "bidirectional"))
      (node (ref "CON_PROG7") (pin "2") (pinfunction "2_2") (pintype "bidirectional"))
      (node (ref "CON_PROG7") (pin "3") (pinfunction "3_3") (pintype "bidirectional"))
      (node (ref "CON_PROG7") (pin "5") (pinfunction "5_5") (pintype "bidirectional"))
      (node (ref "CON_PROG7") (pin "6") (pinfunction "6_6") (pintype "bidirectional"))
      (node (ref "CON_PROG8") (pin "16") (pinfunction "16_16") (pintype "bidirectional"))
      (node (ref "CON_PROG8") (pin "2") (pinfunction "2_2") (pintype "bidirectional"))
      (node (ref "CON_PROG8") (pin "3") (pinfunction "3_3") (pintype "bidirectional"))
      (node (ref "CON_PROG8") (pin "5") (pinfunction "5_5") (pintype "bidirectional"))
      (node (ref "CON_PROG8") (pin "6") (pinfunction "6_6") (pintype "bidirectional"))
      (node (ref "CON_PROG9") (pin "16") (pinfunction "16_16") (pintype "bidirectional"))
      (node (ref "CON_PROG9") (pin "2") (pinfunction "2_2") (pintype "bidirectional"))
      (node (ref "CON_PROG9") (pin "3") (pinfunction "3_3") (pintype "bidirectional"))
      (node (ref "CON_PROG9") (pin "5") (pinfunction "5_5") (pintype "bidirectional"))
      (node (ref "CON_PROG9") (pin "6") (pinfunction "6_6") (pintype "bidirectional"))
      (node (ref "H1") (pin "B3,3") (pinfunction "MOUNT_B3,3") (pintype "passive"))
      (node (ref "H2") (pin "B3,3") (pinfunction "MOUNT_B3,3") (pintype "passive"))
      (node (ref "H3") (pin "B3,3") (pinfunction "MOUNT_B3,3") (pintype "passive"))
      (node (ref "H4") (pin "B3,3") (pinfunction "MOUNT_B3,3") (pintype "passive"))
      (node (ref "IC1") (pin "1") (pinfunction "ADJ_1") (pintype "input"))
      (node (ref "IC100") (pin "22") (pinfunction "GND_22") (pintype "power_in"))
      (node (ref "IC100") (pin "8") (pinfunction "GND_8") (pintype "power_in"))
      (node (ref "IC2") (pin "1") (pinfunction "GND_1") (pintype "input"))
      (node (ref "ISP") (pin "10") (pinfunction "10_10") (pintype "passive"))
      (node (ref "ISP") (pin "4") (pinfunction "4_4") (pintype "passive"))
      (node (ref "ISP") (pin "6") (pinfunction "6_6") (pintype "passive"))
      (node (ref "ISP") (pin "8") (pinfunction "8_8") (pintype "passive"))
      (node (ref "LCD") (pin "1") (pinfunction "1_1") (pintype "passive"))
      (node (ref "LCD") (pin "16") (pinfunction "16_16") (pintype "passive"))
      (node (ref "LCD") (pin "5") (pinfunction "5_5") (pintype "passive"))
      (node (ref "R10") (pin "2") (pinfunction "2_2") (pintype "passive"))
      (node (ref "R12") (pin "2") (pinfunction "2_2") (pintype "passive"))
      (node (ref "R14") (pin "2") (pinfunction "2_2") (pintype "passive"))
      (node (ref "R16") (pin "2") (pinfunction "2_2") (pintype "passive"))
      (node (ref "R18") (pin "2") (pinfunction "2_2") (pintype "passive"))
      (node (ref "R20") (pin "2") (pinfunction "2_2") (pintype "passive"))
      (node (ref "R22") (pin "2") (pinfunction "2_2") (pintype "passive"))
      (node (ref "R24") (pin "2") (pinfunction "2_2") (pintype "passive"))
      (node (ref "R26") (pin "2") (pinfunction "2_2") (pintype "passive"))
      (node (ref "R28") (pin "2") (pinfunction "2_2") (pintype "passive"))
      (node (ref "R30") (pin "2") (pinfunction "2_2") (pintype "passive"))
      (node (ref "R32") (pin "2") (pinfunction "2_2") (pintype "passive"))
      (node (ref "R34") (pin "2") (pinfunction "2_2") (pintype "passive"))
      (node (ref "R36") (pin "2") (pinfunction "2_2") (pintype "passive"))
      (node (ref "R38") (pin "2") (pinfunction "2_2") (pintype "passive"))
      (node (ref "R40") (pin "2") (pinfunction "2_2") (pintype "passive"))
      (node (ref "R42") (pin "2") (pinfunction "2_2") (pintype "passive"))
      (node (ref "R44") (pin "2") (pinfunction "2_2") (pintype "passive"))
      (node (ref "SUPPLY") (pin "L1") (pinfunction "P1_L1") (pintype "bidirectional"))
      (node (ref "T1") (pin "A") (pinfunction "P_A") (pintype "passive"))
      (node (ref "T1") (pin "A'") (pinfunction "P_A'") (pintype "passive"))
      (node (ref "T2") (pin "A") (pinfunction "P_A") (pintype "passive"))
      (node (ref "T2") (pin "A'") (pinfunction "P_A'") (pintype "passive"))
      (node (ref "T3") (pin "A") (pinfunction "P_A") (pintype "passive"))
      (node (ref "T3") (pin "A'") (pinfunction "P_A'") (pintype "passive"))
      (node (ref "T4") (pin "A") (pinfunction "P_A") (pintype "passive"))
      (node (ref "T4") (pin "A'") (pinfunction "P_A'") (pintype "passive"))
      (node (ref "U1") (pin "2") (pinfunction "VSS_2") (pintype "power_in"))
      (node (ref "U10") (pin "2") (pinfunction "VSS_2") (pintype "power_in"))
      (node (ref "U11") (pin "2") (pinfunction "VSS_2") (pintype "power_in"))
      (node (ref "U12") (pin "2") (pinfunction "VSS_2") (pintype "power_in"))
      (node (ref "U13") (pin "2") (pinfunction "VSS_2") (pintype "power_in"))
      (node (ref "U14") (pin "2") (pinfunction "VSS_2") (pintype "power_in"))
      (node (ref "U15") (pin "2") (pinfunction "VSS_2") (pintype "power_in"))
      (node (ref "U16") (pin "2") (pinfunction "VSS_2") (pintype "power_in"))
      (node (ref "U17") (pin "2") (pinfunction "VSS_2") (pintype "power_in"))
      (node (ref "U18") (pin "2") (pinfunction "VSS_2") (pintype "power_in"))
      (node (ref "U2") (pin "2") (pinfunction "VSS_2") (pintype "power_in"))
      (node (ref "U3") (pin "2") (pinfunction "VSS_2") (pintype "power_in"))
      (node (ref "U4") (pin "2") (pinfunction "VSS_2") (pintype "power_in"))
      (node (ref "U5") (pin "2") (pinfunction "VSS_2") (pintype "power_in"))
      (node (ref "U6") (pin "2") (pinfunction "VSS_2") (pintype "power_in"))
      (node (ref "U7") (pin "2") (pinfunction "VSS_2") (pintype "power_in"))
      (node (ref "U8") (pin "2") (pinfunction "VSS_2") (pintype "power_in"))
      (node (ref "U9") (pin "2") (pinfunction "VSS_2") (pintype "power_in"))
    )
    (net (code "10") (name "MISO") (class "Default")
      (node (ref "IC100") (pin "18") (pinfunction "PB4(MISO)_18") (pintype "bidirectional"))
      (node (ref "ISP") (pin "9") (pinfunction "9_9") (pintype "passive"))
    )
    (net (code "11") (name "MOSI") (class "Default")
      (node (ref "IC100") (pin "17") (pinfunction "PB3(MOSI/OC2)_17") (pintype "bidirectional"))
      (node (ref "ISP") (pin "1") (pinfunction "1_1") (pintype "passive"))
    )
    (net (code "12") (name "Net-(D1-PadA)") (class "Default")
      (node (ref "D1") (pin "A") (pinfunction "A_A") (pintype "passive"))
      (node (ref "R9") (pin "2") (pinfunction "2_2") (pintype "passive"))
    )
    (net (code "13") (name "Net-(D2-PadA)") (class "Default")
      (node (ref "D2") (pin "A") (pinfunction "A_A") (pintype "passive"))
      (node (ref "R11") (pin "2") (pinfunction "2_2") (pintype "passive"))
    )
    (net (code "14") (name "Net-(D3-PadA)") (class "Default")
      (node (ref "D3") (pin "A") (pinfunction "A_A") (pintype "passive"))
      (node (ref "R13") (pin "2") (pinfunction "2_2") (pintype "passive"))
    )
    (net (code "15") (name "Net-(D4-PadA)") (class "Default")
      (node (ref "D4") (pin "A") (pinfunction "A_A") (pintype "passive"))
      (node (ref "R15") (pin "2") (pinfunction "2_2") (pintype "passive"))
    )
    (net (code "16") (name "Net-(D5-PadA)") (class "Default")
      (node (ref "D5") (pin "A") (pinfunction "A_A") (pintype "passive"))
      (node (ref "R17") (pin "2") (pinfunction "2_2") (pintype "passive"))
    )
    (net (code "17") (name "Net-(D6-PadA)") (class "Default")
      (node (ref "D6") (pin "A") (pinfunction "A_A") (pintype "passive"))
      (node (ref "R19") (pin "2") (pinfunction "2_2") (pintype "passive"))
    )
    (net (code "18") (name "Net-(D7-PadA)") (class "Default")
      (node (ref "D7") (pin "A") (pinfunction "A_A") (pintype "passive"))
      (node (ref "R21") (pin "2") (pinfunction "2_2") (pintype "passive"))
    )
    (net (code "19") (name "Net-(D8-PadA)") (class "Default")
      (node (ref "D8") (pin "A") (pinfunction "A_A") (pintype "passive"))
      (node (ref "R23") (pin "2") (pinfunction "2_2") (pintype "passive"))
    )
    (net (code "20") (name "Net-(D9-PadA)") (class "Default")
      (node (ref "D9") (pin "A") (pinfunction "A_A") (pintype "passive"))
      (node (ref "R25") (pin "2") (pinfunction "2_2") (pintype "passive"))
    )
    (net (code "21") (name "Net-(D10-PadA)") (class "Default")
      (node (ref "D10") (pin "A") (pinfunction "A_A") (pintype "passive"))
      (node (ref "R27") (pin "2") (pinfunction "2_2") (pintype "passive"))
    )
    (net (code "22") (name "Net-(D11-PadA)") (class "Default")
      (node (ref "D11") (pin "A") (pinfunction "A_A") (pintype "passive"))
      (node (ref "R29") (pin "2") (pinfunction "2_2") (pintype "passive"))
    )
    (net (code "23") (name "Net-(D12-PadA)") (class "Default")
      (node (ref "D12") (pin "A") (pinfunction "A_A") (pintype "passive"))
      (node (ref "R31") (pin "2") (pinfunction "2_2") (pintype "passive"))
    )
    (net (code "24") (name "Net-(D13-PadA)") (class "Default")
      (node (ref "D13") (pin "A") (pinfunction "A_A") (pintype "passive"))
      (node (ref "R33") (pin "2") (pinfunction "2_2") (pintype "passive"))
    )
    (net (code "25") (name "Net-(D14-PadA)") (class "Default")
      (node (ref "D14") (pin "A") (pinfunction "A_A") (pintype "passive"))
      (node (ref "R35") (pin "2") (pinfunction "2_2") (pintype "passive"))
    )
    (net (code "26") (name "Net-(D15-PadA)") (class "Default")
      (node (ref "D15") (pin "A") (pinfunction "A_A") (pintype "passive"))
      (node (ref "R37") (pin "2") (pinfunction "2_2") (pintype "passive"))
    )
    (net (code "27") (name "Net-(D16-PadA)") (class "Default")
      (node (ref "D16") (pin "A") (pinfunction "A_A") (pintype "passive"))
      (node (ref "R39") (pin "2") (pinfunction "2_2") (pintype "passive"))
    )
    (net (code "28") (name "Net-(D17-PadA)") (class "Default")
      (node (ref "D17") (pin "A") (pinfunction "A_A") (pintype "passive"))
      (node (ref "R41") (pin "2") (pinfunction "2_2") (pintype "passive"))
    )
    (net (code "29") (name "Net-(D18-PadA)") (class "Default")
      (node (ref "D18") (pin "A") (pinfunction "A_A") (pintype "passive"))
      (node (ref "R43") (pin "2") (pinfunction "2_2") (pintype "passive"))
    )
    (net (code "30") (name "Net-(LCD-Pad15)") (class "Default")
      (node (ref "LCD") (pin "15") (pinfunction "15_15") (pintype "passive"))
      (node (ref "R5") (pin "2") (pinfunction "2_2") (pintype "passive"))
    )
    (net (code "31") (name "Net-(U1-PROG)") (class "Default")
      (node (ref "R10") (pin "1") (pinfunction "1_1") (pintype "passive"))
      (node (ref "U1") (pin "5") (pinfunction "PROG_5") (pintype "input"))
    )
    (net (code "32") (name "Net-(U1-STAT)") (class "Default")
      (node (ref "D1") (pin "C") (pinfunction "C_C") (pintype "passive"))
      (node (ref "U1") (pin "1") (pinfunction "STAT_1") (pintype "output"))
    )
    (net (code "33") (name "Net-(U1-VBAT)") (class "Default")
      (node (ref "C6") (pin "1") (pinfunction "1_1") (pintype "passive"))
      (node (ref "CON_PROG1") (pin "15") (pinfunction "15_15") (pintype "bidirectional"))
      (node (ref "U1") (pin "3") (pinfunction "VBAT_3") (pintype "power_in"))
    )
    (net (code "34") (name "Net-(U2-PROG)") (class "Default")
      (node (ref "R12") (pin "1") (pinfunction "1_1") (pintype "passive"))
      (node (ref "U2") (pin "5") (pinfunction "PROG_5") (pintype "input"))
    )
    (net (code "35") (name "Net-(U2-STAT)") (class "Default")
      (node (ref "D2") (pin "C") (pinfunction "C_C") (pintype "passive"))
      (node (ref "U2") (pin "1") (pinfunction "STAT_1") (pintype "output"))
    )
    (net (code "36") (name "Net-(U2-VBAT)") (class "Default")
      (node (ref "C7") (pin "1") (pinfunction "1_1") (pintype "passive"))
      (node (ref "CON_PROG1") (pin "14") (pinfunction "14_14") (pintype "bidirectional"))
      (node (ref "U2") (pin "3") (pinfunction "VBAT_3") (pintype "power_in"))
    )
    (net (code "37") (name "Net-(U3-PROG)") (class "Default")
      (node (ref "R14") (pin "1") (pinfunction "1_1") (pintype "passive"))
      (node (ref "U3") (pin "5") (pinfunction "PROG_5") (pintype "input"))
    )
    (net (code "38") (name "Net-(U3-STAT)") (class "Default")
      (node (ref "D3") (pin "C") (pinfunction "C_C") (pintype "passive"))
      (node (ref "U3") (pin "1") (pinfunction "STAT_1") (pintype "output"))
    )
    (net (code "39") (name "Net-(U3-VBAT)") (class "Default")
      (node (ref "C8") (pin "1") (pinfunction "1_1") (pintype "passive"))
      (node (ref "CON_PROG2") (pin "14") (pinfunction "14_14") (pintype "bidirectional"))
      (node (ref "U3") (pin "3") (pinfunction "VBAT_3") (pintype "power_in"))
    )
    (net (code "40") (name "Net-(U4-PROG)") (class "Default")
      (node (ref "R16") (pin "1") (pinfunction "1_1") (pintype "passive"))
      (node (ref "U4") (pin "5") (pinfunction "PROG_5") (pintype "input"))
    )
    (net (code "41") (name "Net-(U4-STAT)") (class "Default")
      (node (ref "D4") (pin "C") (pinfunction "C_C") (pintype "passive"))
      (node (ref "U4") (pin "1") (pinfunction "STAT_1") (pintype "output"))
    )
    (net (code "42") (name "Net-(U4-VBAT)") (class "Default")
      (node (ref "C9") (pin "1") (pinfunction "1_1") (pintype "passive"))
      (node (ref "CON_PROG2") (pin "15") (pinfunction "15_15") (pintype "bidirectional"))
      (node (ref "U4") (pin "3") (pinfunction "VBAT_3") (pintype "power_in"))
    )
    (net (code "43") (name "Net-(U5-PROG)") (class "Default")
      (node (ref "R18") (pin "1") (pinfunction "1_1") (pintype "passive"))
      (node (ref "U5") (pin "5") (pinfunction "PROG_5") (pintype "input"))
    )
    (net (code "44") (name "Net-(U5-STAT)") (class "Default")
      (node (ref "D5") (pin "C") (pinfunction "C_C") (pintype "passive"))
      (node (ref "U5") (pin "1") (pinfunction "STAT_1") (pintype "output"))
    )
    (net (code "45") (name "Net-(U5-VBAT)") (class "Default")
      (node (ref "C10") (pin "1") (pinfunction "1_1") (pintype "passive"))
      (node (ref "CON_PROG3") (pin "14") (pinfunction "14_14") (pintype "bidirectional"))
      (node (ref "U5") (pin "3") (pinfunction "VBAT_3") (pintype "power_in"))
    )
    (net (code "46") (name "Net-(U6-PROG)") (class "Default")
      (node (ref "R20") (pin "1") (pinfunction "1_1") (pintype "passive"))
      (node (ref "U6") (pin "5") (pinfunction "PROG_5") (pintype "input"))
    )
    (net (code "47") (name "Net-(U6-STAT)") (class "Default")
      (node (ref "D6") (pin "C") (pinfunction "C_C") (pintype "passive"))
      (node (ref "U6") (pin "1") (pinfunction "STAT_1") (pintype "output"))
    )
    (net (code "48") (name "Net-(U6-VBAT)") (class "Default")
      (node (ref "C11") (pin "1") (pinfunction "1_1") (pintype "passive"))
      (node (ref "CON_PROG3") (pin "15") (pinfunction "15_15") (pintype "bidirectional"))
      (node (ref "U6") (pin "3") (pinfunction "VBAT_3") (pintype "power_in"))
    )
    (net (code "49") (name "Net-(U7-PROG)") (class "Default")
      (node (ref "R22") (pin "1") (pinfunction "1_1") (pintype "passive"))
      (node (ref "U7") (pin "5") (pinfunction "PROG_5") (pintype "input"))
    )
    (net (code "50") (name "Net-(U7-STAT)") (class "Default")
      (node (ref "D7") (pin "C") (pinfunction "C_C") (pintype "passive"))
      (node (ref "U7") (pin "1") (pinfunction "STAT_1") (pintype "output"))
    )
    (net (code "51") (name "Net-(U7-VBAT)") (class "Default")
      (node (ref "C12") (pin "1") (pinfunction "1_1") (pintype "passive"))
      (node (ref "CON_PROG4") (pin "14") (pinfunction "14_14") (pintype "bidirectional"))
      (node (ref "U7") (pin "3") (pinfunction "VBAT_3") (pintype "power_in"))
    )
    (net (code "52") (name "Net-(U8-PROG)") (class "Default")
      (node (ref "R24") (pin "1") (pinfunction "1_1") (pintype "passive"))
      (node (ref "U8") (pin "5") (pinfunction "PROG_5") (pintype "input"))
    )
    (net (code "53") (name "Net-(U8-STAT)") (class "Default")
      (node (ref "D8") (pin "C") (pinfunction "C_C") (pintype "passive"))
      (node (ref "U8") (pin "1") (pinfunction "STAT_1") (pintype "output"))
    )
    (net (code "54") (name "Net-(U8-VBAT)") (class "Default")
      (node (ref "C13") (pin "1") (pinfunction "1_1") (pintype "passive"))
      (node (ref "CON_PROG4") (pin "15") (pinfunction "15_15") (pintype "bidirectional"))
      (node (ref "U8") (pin "3") (pinfunction "VBAT_3") (pintype "power_in"))
    )
    (net (code "55") (name "Net-(U9-PROG)") (class "Default")
      (node (ref "R26") (pin "1") (pinfunction "1_1") (pintype "passive"))
      (node (ref "U9") (pin "5") (pinfunction "PROG_5") (pintype "input"))
    )
    (net (code "56") (name "Net-(U9-STAT)") (class "Default")
      (node (ref "D9") (pin "C") (pinfunction "C_C") (pintype "passive"))
      (node (ref "U9") (pin "1") (pinfunction "STAT_1") (pintype "output"))
    )
    (net (code "57") (name "Net-(U9-VBAT)") (class "Default")
      (node (ref "C14") (pin "1") (pinfunction "1_1") (pintype "passive"))
      (node (ref "CON_PROG5") (pin "14") (pinfunction "14_14") (pintype "bidirectional"))
      (node (ref "U9") (pin "3") (pinfunction "VBAT_3") (pintype "power_in"))
    )
    (net (code "58") (name "Net-(U10-PROG)") (class "Default")
      (node (ref "R28") (pin "1") (pinfunction "1_1") (pintype "passive"))
      (node (ref "U10") (pin "5") (pinfunction "PROG_5") (pintype "input"))
    )
    (net (code "59") (name "Net-(U10-STAT)") (class "Default")
      (node (ref "D10") (pin "C") (pinfunction "C_C") (pintype "passive"))
      (node (ref "U10") (pin "1") (pinfunction "STAT_1") (pintype "output"))
    )
    (net (code "60") (name "Net-(U10-VBAT)") (class "Default")
      (node (ref "C15") (pin "1") (pinfunction "1_1") (pintype "passive"))
      (node (ref "CON_PROG5") (pin "15") (pinfunction "15_15") (pintype "bidirectional"))
      (node (ref "U10") (pin "3") (pinfunction "VBAT_3") (pintype "power_in"))
    )
    (net (code "61") (name "Net-(U11-PROG)") (class "Default")
      (node (ref "R30") (pin "1") (pinfunction "1_1") (pintype "passive"))
      (node (ref "U11") (pin "5") (pinfunction "PROG_5") (pintype "input"))
    )
    (net (code "62") (name "Net-(U11-STAT)") (class "Default")
      (node (ref "D11") (pin "C") (pinfunction "C_C") (pintype "passive"))
      (node (ref "U11") (pin "1") (pinfunction "STAT_1") (pintype "output"))
    )
    (net (code "63") (name "Net-(U11-VBAT)") (class "Default")
      (node (ref "C16") (pin "1") (pinfunction "1_1") (pintype "passive"))
      (node (ref "CON_PROG7") (pin "14") (pinfunction "14_14") (pintype "bidirectional"))
      (node (ref "U11") (pin "3") (pinfunction "VBAT_3") (pintype "power_in"))
    )
    (net (code "64") (name "Net-(U12-PROG)") (class "Default")
      (node (ref "R32") (pin "1") (pinfunction "1_1") (pintype "passive"))
      (node (ref "U12") (pin "5") (pinfunction "PROG_5") (pintype "input"))
    )
    (net (code "65") (name "Net-(U12-STAT)") (class "Default")
      (node (ref "D12") (pin "C") (pinfunction "C_C") (pintype "passive"))
      (node (ref "U12") (pin "1") (pinfunction "STAT_1") (pintype "output"))
    )
    (net (code "66") (name "Net-(U12-VBAT)") (class "Default")
      (node (ref "C17") (pin "1") (pinfunction "1_1") (pintype "passive"))
      (node (ref "CON_PROG7") (pin "15") (pinfunction "15_15") (pintype "bidirectional"))
      (node (ref "U12") (pin "3") (pinfunction "VBAT_3") (pintype "power_in"))
    )
    (net (code "67") (name "Net-(U13-PROG)") (class "Default")
      (node (ref "R34") (pin "1") (pinfunction "1_1") (pintype "passive"))
      (node (ref "U13") (pin "5") (pinfunction "PROG_5") (pintype "input"))
    )
    (net (code "68") (name "Net-(U13-STAT)") (class "Default")
      (node (ref "D13") (pin "C") (pinfunction "C_C") (pintype "passive"))
      (node (ref "U13") (pin "1") (pinfunction "STAT_1") (pintype "output"))
    )
    (net (code "69") (name "Net-(U13-VBAT)") (class "Default")
      (node (ref "C18") (pin "1") (pinfunction "1_1") (pintype "passive"))
      (node (ref "CON_PROG8") (pin "14") (pinfunction "14_14") (pintype "bidirectional"))
      (node (ref "U13") (pin "3") (pinfunction "VBAT_3") (pintype "power_in"))
    )
    (net (code "70") (name "Net-(U14-PROG)") (class "Default")
      (node (ref "R36") (pin "1") (pinfunction "1_1") (pintype "passive"))
      (node (ref "U14") (pin "5") (pinfunction "PROG_5") (pintype "input"))
    )
    (net (code "71") (name "Net-(U14-STAT)") (class "Default")
      (node (ref "D14") (pin "C") (pinfunction "C_C") (pintype "passive"))
      (node (ref "U14") (pin "1") (pinfunction "STAT_1") (pintype "output"))
    )
    (net (code "72") (name "Net-(U14-VBAT)") (class "Default")
      (node (ref "C19") (pin "1") (pinfunction "1_1") (pintype "passive"))
      (node (ref "CON_PROG8") (pin "15") (pinfunction "15_15") (pintype "bidirectional"))
      (node (ref "U14") (pin "3") (pinfunction "VBAT_3") (pintype "power_in"))
    )
    (net (code "73") (name "Net-(U15-PROG)") (class "Default")
      (node (ref "R38") (pin "1") (pinfunction "1_1") (pintype "passive"))
      (node (ref "U15") (pin "5") (pinfunction "PROG_5") (pintype "input"))
    )
    (net (code "74") (name "Net-(U15-STAT)") (class "Default")
      (node (ref "D15") (pin "C") (pinfunction "C_C") (pintype "passive"))
      (node (ref "U15") (pin "1") (pinfunction "STAT_1") (pintype "output"))
    )
    (net (code "75") (name "Net-(U15-VBAT)") (class "Default")
      (node (ref "C20") (pin "1") (pinfunction "1_1") (pintype "passive"))
      (node (ref "CON_PROG9") (pin "14") (pinfunction "14_14") (pintype "bidirectional"))
      (node (ref "U15") (pin "3") (pinfunction "VBAT_3") (pintype "power_in"))
    )
    (net (code "76") (name "Net-(U16-PROG)") (class "Default")
      (node (ref "R40") (pin "1") (pinfunction "1_1") (pintype "passive"))
      (node (ref "U16") (pin "5") (pinfunction "PROG_5") (pintype "input"))
    )
    (net (code "77") (name "Net-(U16-STAT)") (class "Default")
      (node (ref "D16") (pin "C") (pinfunction "C_C") (pintype "passive"))
      (node (ref "U16") (pin "1") (pinfunction "STAT_1") (pintype "output"))
    )
    (net (code "78") (name "Net-(U16-VBAT)") (class "Default")
      (node (ref "C21") (pin "1") (pinfunction "1_1") (pintype "passive"))
      (node (ref "CON_PROG9") (pin "15") (pinfunction "15_15") (pintype "bidirectional"))
      (node (ref "U16") (pin "3") (pinfunction "VBAT_3") (pintype "power_in"))
    )
    (net (code "79") (name "Net-(U17-PROG)") (class "Default")
      (node (ref "R42") (pin "1") (pinfunction "1_1") (pintype "passive"))
      (node (ref "U17") (pin "5") (pinfunction "PROG_5") (pintype "input"))
    )
    (net (code "80") (name "Net-(U17-STAT)") (class "Default")
      (node (ref "D17") (pin "C") (pinfunction "C_C") (pintype "passive"))
      (node (ref "U17") (pin "1") (pinfunction "STAT_1") (pintype "output"))
    )
    (net (code "81") (name "Net-(U17-VBAT)") (class "Default")
      (node (ref "C22") (pin "1") (pinfunction "1_1") (pintype "passive"))
      (node (ref "CON_PROG6") (pin "14") (pinfunction "14_14") (pintype "bidirectional"))
      (node (ref "U17") (pin "3") (pinfunction "VBAT_3") (pintype "power_in"))
    )
    (net (code "82") (name "Net-(U18-PROG)") (class "Default")
      (node (ref "R44") (pin "1") (pinfunction "1_1") (pintype "passive"))
      (node (ref "U18") (pin "5") (pinfunction "PROG_5") (pintype "input"))
    )
    (net (code "83") (name "Net-(U18-STAT)") (class "Default")
      (node (ref "D18") (pin "C") (pinfunction "C_C") (pintype "passive"))
      (node (ref "U18") (pin "1") (pinfunction "STAT_1") (pintype "output"))
    )
    (net (code "84") (name "Net-(U18-VBAT)") (class "Default")
      (node (ref "C23") (pin "1") (pinfunction "1_1") (pintype "passive"))
      (node (ref "CON_PROG6") (pin "15") (pinfunction "15_15") (pintype "bidirectional"))
      (node (ref "U18") (pin "3") (pinfunction "VBAT_3") (pintype "power_in"))
    )
    (net (code "85") (name "RESET") (class "Default")
      (node (ref "IC100") (pin "1") (pinfunction "PC6(/RESET)_1") (pintype "bidirectional"))
      (node (ref "ISP") (pin "5") (pinfunction "5_5") (pintype "passive"))
      (node (ref "R6") (pin "2") (pinfunction "2_2") (pintype "passive"))
    )
    (net (code "86") (name "RS") (class "Default")
      (node (ref "IC100") (pin "12") (pinfunction "PD6(AIN0)_12") (pintype "bidirectional"))
      (node (ref "LCD") (pin "4") (pinfunction "4_4") (pintype "passive"))
    )
    (net (code "87") (name "RXD") (class "Default")
      (node (ref "IC100") (pin "2") (pinfunction "PD0(RXD)_2") (pintype "bidirectional"))
    )
    (net (code "88") (name "SCK") (class "Default")
      (node (ref "IC100") (pin "19") (pinfunction "PB5(SCK)_19") (pintype "bidirectional"))
      (node (ref "ISP") (pin "7") (pinfunction "7_7") (pintype "passive"))
    )
    (net (code "89") (name "SCL") (class "Default")
      (node (ref "CON_PROG1") (pin "8") (pinfunction "8_8") (pintype "bidirectional"))
      (node (ref "CON_PROG2") (pin "8") (pinfunction "8_8") (pintype "bidirectional"))
      (node (ref "CON_PROG3") (pin "8") (pinfunction "8_8") (pintype "bidirectional"))
      (node (ref "CON_PROG4") (pin "8") (pinfunction "8_8") (pintype "bidirectional"))
      (node (ref "CON_PROG5") (pin "8") (pinfunction "8_8") (pintype "bidirectional"))
      (node (ref "CON_PROG6") (pin "8") (pinfunction "8_8") (pintype "bidirectional"))
      (node (ref "CON_PROG7") (pin "8") (pinfunction "8_8") (pintype "bidirectional"))
      (node (ref "CON_PROG8") (pin "8") (pinfunction "8_8") (pintype "bidirectional"))
      (node (ref "CON_PROG9") (pin "8") (pinfunction "8_8") (pintype "bidirectional"))
      (node (ref "IC100") (pin "28") (pinfunction "PC5(ADC5/SCL)_28") (pintype "bidirectional"))
      (node (ref "R4") (pin "1") (pinfunction "1_1") (pintype "passive"))
    )
    (net (code "90") (name "SDA") (class "Default")
      (node (ref "CON_PROG1") (pin "9") (pinfunction "9_9") (pintype "bidirectional"))
      (node (ref "CON_PROG2") (pin "9") (pinfunction "9_9") (pintype "bidirectional"))
      (node (ref "CON_PROG3") (pin "9") (pinfunction "9_9") (pintype "bidirectional"))
      (node (ref "CON_PROG4") (pin "9") (pinfunction "9_9") (pintype "bidirectional"))
      (node (ref "CON_PROG5") (pin "9") (pinfunction "9_9") (pintype "bidirectional"))
      (node (ref "CON_PROG6") (pin "9") (pinfunction "9_9") (pintype "bidirectional"))
      (node (ref "CON_PROG7") (pin "9") (pinfunction "9_9") (pintype "bidirectional"))
      (node (ref "CON_PROG8") (pin "9") (pinfunction "9_9") (pintype "bidirectional"))
      (node (ref "CON_PROG9") (pin "9") (pinfunction "9_9") (pintype "bidirectional"))
      (node (ref "IC100") (pin "27") (pinfunction "PC4(ADC4/SDA)_27") (pintype "bidirectional"))
      (node (ref "R3") (pin "1") (pinfunction "1_1") (pintype "passive"))
    )
    (net (code "91") (name "T1") (class "Default")
      (node (ref "IC100") (pin "4") (pinfunction "PD2(INT0)_4") (pintype "bidirectional"))
      (node (ref "R1") (pin "1") (pinfunction "1_1") (pintype "passive"))
      (node (ref "T1") (pin "B") (pinfunction "S_B") (pintype "passive"))
      (node (ref "T1") (pin "B'") (pinfunction "S_B'") (pintype "passive"))
    )
    (net (code "92") (name "T2") (class "Default")
      (node (ref "IC100") (pin "5") (pinfunction "PD3(INT1)_5") (pintype "bidirectional"))
      (node (ref "R2") (pin "1") (pinfunction "1_1") (pintype "passive"))
      (node (ref "T2") (pin "B") (pinfunction "S_B") (pintype "passive"))
      (node (ref "T2") (pin "B'") (pinfunction "S_B'") (pintype "passive"))
    )
    (net (code "93") (name "T3") (class "Default")
      (node (ref "IC100") (pin "6") (pinfunction "PD4(XCK/T0)_6") (pintype "bidirectional"))
      (node (ref "R7") (pin "1") (pinfunction "1_1") (pintype "passive"))
      (node (ref "T3") (pin "B") (pinfunction "S_B") (pintype "passive"))
      (node (ref "T3") (pin "B'") (pinfunction "S_B'") (pintype "passive"))
    )
    (net (code "94") (name "T4") (class "Default")
      (node (ref "IC100") (pin "11") (pinfunction "PD5(T1)_11") (pintype "bidirectional"))
      (node (ref "R8") (pin "1") (pinfunction "1_1") (pintype "passive"))
      (node (ref "T4") (pin "B") (pinfunction "S_B") (pintype "passive"))
      (node (ref "T4") (pin "B'") (pinfunction "S_B'") (pintype "passive"))
    )
    (net (code "95") (name "TXD") (class "Default")
      (node (ref "IC100") (pin "3") (pinfunction "PD1(TXD)_3") (pintype "bidirectional"))
    )
    (net (code "96") (name "unconnected-(CON_PROG1-Pad4)") (class "Default")
      (node (ref "CON_PROG1") (pin "4") (pinfunction "4_4") (pintype "bidirectional"))
    )
    (net (code "97") (name "unconnected-(CON_PROG1-Pad7)") (class "Default")
      (node (ref "CON_PROG1") (pin "7") (pinfunction "7_7") (pintype "bidirectional"))
    )
    (net (code "98") (name "unconnected-(CON_PROG1-Pad10)") (class "Default")
      (node (ref "CON_PROG1") (pin "10") (pinfunction "10_10") (pintype "bidirectional"))
    )
    (net (code "99") (name "unconnected-(CON_PROG1-Pad11)") (class "Default")
      (node (ref "CON_PROG1") (pin "11") (pinfunction "11_11") (pintype "bidirectional"))
    )
    (net (code "100") (name "unconnected-(CON_PROG1-Pad12)") (class "Default")
      (node (ref "CON_PROG1") (pin "12") (pinfunction "12_12") (pintype "bidirectional"))
    )
    (net (code "101") (name "unconnected-(CON_PROG1-Pad13)") (class "Default")
      (node (ref "CON_PROG1") (pin "13") (pinfunction "13_13") (pintype "bidirectional"))
    )
    (net (code "102") (name "unconnected-(CON_PROG1-Pad17)") (class "Default")
      (node (ref "CON_PROG1") (pin "17") (pinfunction "17_17") (pintype "bidirectional"))
    )
    (net (code "103") (name "unconnected-(CON_PROG1-Pad18)") (class "Default")
      (node (ref "CON_PROG1") (pin "18") (pinfunction "18_18") (pintype "bidirectional"))
    )
    (net (code "104") (name "unconnected-(CON_PROG1-Pad19)") (class "Default")
      (node (ref "CON_PROG1") (pin "19") (pinfunction "19_19") (pintype "bidirectional"))
    )
    (net (code "105") (name "unconnected-(CON_PROG1-Pad20)") (class "Default")
      (node (ref "CON_PROG1") (pin "20") (pinfunction "20_20") (pintype "bidirectional"))
    )
    (net (code "106") (name "unconnected-(CON_PROG2-Pad4)") (class "Default")
      (node (ref "CON_PROG2") (pin "4") (pinfunction "4_4") (pintype "bidirectional"))
    )
    (net (code "107") (name "unconnected-(CON_PROG2-Pad7)") (class "Default")
      (node (ref "CON_PROG2") (pin "7") (pinfunction "7_7") (pintype "bidirectional"))
    )
    (net (code "108") (name "unconnected-(CON_PROG2-Pad10)") (class "Default")
      (node (ref "CON_PROG2") (pin "10") (pinfunction "10_10") (pintype "bidirectional"))
    )
    (net (code "109") (name "unconnected-(CON_PROG2-Pad11)") (class "Default")
      (node (ref "CON_PROG2") (pin "11") (pinfunction "11_11") (pintype "bidirectional"))
    )
    (net (code "110") (name "unconnected-(CON_PROG2-Pad12)") (class "Default")
      (node (ref "CON_PROG2") (pin "12") (pinfunction "12_12") (pintype "bidirectional"))
    )
    (net (code "111") (name "unconnected-(CON_PROG2-Pad13)") (class "Default")
      (node (ref "CON_PROG2") (pin "13") (pinfunction "13_13") (pintype "bidirectional"))
    )
    (net (code "112") (name "unconnected-(CON_PROG2-Pad17)") (class "Default")
      (node (ref "CON_PROG2") (pin "17") (pinfunction "17_17") (pintype "bidirectional"))
    )
    (net (code "113") (name "unconnected-(CON_PROG2-Pad18)") (class "Default")
      (node (ref "CON_PROG2") (pin "18") (pinfunction "18_18") (pintype "bidirectional"))
    )
    (net (code "114") (name "unconnected-(CON_PROG2-Pad19)") (class "Default")
      (node (ref "CON_PROG2") (pin "19") (pinfunction "19_19") (pintype "bidirectional"))
    )
    (net (code "115") (name "unconnected-(CON_PROG2-Pad20)") (class "Default")
      (node (ref "CON_PROG2") (pin "20") (pinfunction "20_20") (pintype "bidirectional"))
    )
    (net (code "116") (name "unconnected-(CON_PROG3-Pad4)") (class "Default")
      (node (ref "CON_PROG3") (pin "4") (pinfunction "4_4") (pintype "bidirectional"))
    )
    (net (code "117") (name "unconnected-(CON_PROG3-Pad7)") (class "Default")
      (node (ref "CON_PROG3") (pin "7") (pinfunction "7_7") (pintype "bidirectional"))
    )
    (net (code "118") (name "unconnected-(CON_PROG3-Pad10)") (class "Default")
      (node (ref "CON_PROG3") (pin "10") (pinfunction "10_10") (pintype "bidirectional"))
    )
    (net (code "119") (name "unconnected-(CON_PROG3-Pad11)") (class "Default")
      (node (ref "CON_PROG3") (pin "11") (pinfunction "11_11") (pintype "bidirectional"))
    )
    (net (code "120") (name "unconnected-(CON_PROG3-Pad12)") (class "Default")
      (node (ref "CON_PROG3") (pin "12") (pinfunction "12_12") (pintype "bidirectional"))
    )
    (net (code "121") (name "unconnected-(CON_PROG3-Pad13)") (class "Default")
      (node (ref "CON_PROG3") (pin "13") (pinfunction "13_13") (pintype "bidirectional"))
    )
    (net (code "122") (name "unconnected-(CON_PROG3-Pad17)") (class "Default")
      (node (ref "CON_PROG3") (pin "17") (pinfunction "17_17") (pintype "bidirectional"))
    )
    (net (code "123") (name "unconnected-(CON_PROG3-Pad18)") (class "Default")
      (node (ref "CON_PROG3") (pin "18") (pinfunction "18_18") (pintype "bidirectional"))
    )
    (net (code "124") (name "unconnected-(CON_PROG3-Pad19)") (class "Default")
      (node (ref "CON_PROG3") (pin "19") (pinfunction "19_19") (pintype "bidirectional"))
    )
    (net (code "125") (name "unconnected-(CON_PROG3-Pad20)") (class "Default")
      (node (ref "CON_PROG3") (pin "20") (pinfunction "20_20") (pintype "bidirectional"))
    )
    (net (code "126") (name "unconnected-(CON_PROG4-Pad4)") (class "Default")
      (node (ref "CON_PROG4") (pin "4") (pinfunction "4_4") (pintype "bidirectional"))
    )
    (net (code "127") (name "unconnected-(CON_PROG4-Pad7)") (class "Default")
      (node (ref "CON_PROG4") (pin "7") (pinfunction "7_7") (pintype "bidirectional"))
    )
    (net (code "128") (name "unconnected-(CON_PROG4-Pad10)") (class "Default")
      (node (ref "CON_PROG4") (pin "10") (pinfunction "10_10") (pintype "bidirectional"))
    )
    (net (code "129") (name "unconnected-(CON_PROG4-Pad11)") (class "Default")
      (node (ref "CON_PROG4") (pin "11") (pinfunction "11_11") (pintype "bidirectional"))
    )
    (net (code "130") (name "unconnected-(CON_PROG4-Pad12)") (class "Default")
      (node (ref "CON_PROG4") (pin "12") (pinfunction "12_12") (pintype "bidirectional"))
    )
    (net (code "131") (name "unconnected-(CON_PROG4-Pad13)") (class "Default")
      (node (ref "CON_PROG4") (pin "13") (pinfunction "13_13") (pintype "bidirectional"))
    )
    (net (code "132") (name "unconnected-(CON_PROG4-Pad17)") (class "Default")
      (node (ref "CON_PROG4") (pin "17") (pinfunction "17_17") (pintype "bidirectional"))
    )
    (net (code "133") (name "unconnected-(CON_PROG4-Pad18)") (class "Default")
      (node (ref "CON_PROG4") (pin "18") (pinfunction "18_18") (pintype "bidirectional"))
    )
    (net (code "134") (name "unconnected-(CON_PROG4-Pad19)") (class "Default")
      (node (ref "CON_PROG4") (pin "19") (pinfunction "19_19") (pintype "bidirectional"))
    )
    (net (code "135") (name "unconnected-(CON_PROG4-Pad20)") (class "Default")
      (node (ref "CON_PROG4") (pin "20") (pinfunction "20_20") (pintype "bidirectional"))
    )
    (net (code "136") (name "unconnected-(CON_PROG5-Pad4)") (class "Default")
      (node (ref "CON_PROG5") (pin "4") (pinfunction "4_4") (pintype "bidirectional"))
    )
    (net (code "137") (name "unconnected-(CON_PROG5-Pad7)") (class "Default")
      (node (ref "CON_PROG5") (pin "7") (pinfunction "7_7") (pintype "bidirectional"))
    )
    (net (code "138") (name "unconnected-(CON_PROG5-Pad10)") (class "Default")
      (node (ref "CON_PROG5") (pin "10") (pinfunction "10_10") (pintype "bidirectional"))
    )
    (net (code "139") (name "unconnected-(CON_PROG5-Pad11)") (class "Default")
      (node (ref "CON_PROG5") (pin "11") (pinfunction "11_11") (pintype "bidirectional"))
    )
    (net (code "140") (name "unconnected-(CON_PROG5-Pad12)") (class "Default")
      (node (ref "CON_PROG5") (pin "12") (pinfunction "12_12") (pintype "bidirectional"))
    )
    (net (code "141") (name "unconnected-(CON_PROG5-Pad13)") (class "Default")
      (node (ref "CON_PROG5") (pin "13") (pinfunction "13_13") (pintype "bidirectional"))
    )
    (net (code "142") (name "unconnected-(CON_PROG5-Pad17)") (class "Default")
      (node (ref "CON_PROG5") (pin "17") (pinfunction "17_17") (pintype "bidirectional"))
    )
    (net (code "143") (name "unconnected-(CON_PROG5-Pad18)") (class "Default")
      (node (ref "CON_PROG5") (pin "18") (pinfunction "18_18") (pintype "bidirectional"))
    )
    (net (code "144") (name "unconnected-(CON_PROG5-Pad19)") (class "Default")
      (node (ref "CON_PROG5") (pin "19") (pinfunction "19_19") (pintype "bidirectional"))
    )
    (net (code "145") (name "unconnected-(CON_PROG5-Pad20)") (class "Default")
      (node (ref "CON_PROG5") (pin "20") (pinfunction "20_20") (pintype "bidirectional"))
    )
    (net (code "146") (name "unconnected-(CON_PROG6-Pad4)") (class "Default")
      (node (ref "CON_PROG6") (pin "4") (pinfunction "4_4") (pintype "bidirectional"))
    )
    (net (code "147") (name "unconnected-(CON_PROG6-Pad7)") (class "Default")
      (node (ref "CON_PROG6") (pin "7") (pinfunction "7_7") (pintype "bidirectional"))
    )
    (net (code "148") (name "unconnected-(CON_PROG6-Pad10)") (class "Default")
      (node (ref "CON_PROG6") (pin "10") (pinfunction "10_10") (pintype "bidirectional"))
    )
    (net (code "149") (name "unconnected-(CON_PROG6-Pad11)") (class "Default")
      (node (ref "CON_PROG6") (pin "11") (pinfunction "11_11") (pintype "bidirectional"))
    )
    (net (code "150") (name "unconnected-(CON_PROG6-Pad12)") (class "Default")
      (node (ref "CON_PROG6") (pin "12") (pinfunction "12_12") (pintype "bidirectional"))
    )
    (net (code "151") (name "unconnected-(CON_PROG6-Pad13)") (class "Default")
      (node (ref "CON_PROG6") (pin "13") (pinfunction "13_13") (pintype "bidirectional"))
    )
    (net (code "152") (name "unconnected-(CON_PROG6-Pad17)") (class "Default")
      (node (ref "CON_PROG6") (pin "17") (pinfunction "17_17") (pintype "bidirectional"))
    )
    (net (code "153") (name "unconnected-(CON_PROG6-Pad18)") (class "Default")
      (node (ref "CON_PROG6") (pin "18") (pinfunction "18_18") (pintype "bidirectional"))
    )
    (net (code "154") (name "unconnected-(CON_PROG6-Pad19)") (class "Default")
      (node (ref "CON_PROG6") (pin "19") (pinfunction "19_19") (pintype "bidirectional"))
    )
    (net (code "155") (name "unconnected-(CON_PROG6-Pad20)") (class "Default")
      (node (ref "CON_PROG6") (pin "20") (pinfunction "20_20") (pintype "bidirectional"))
    )
    (net (code "156") (name "unconnected-(CON_PROG7-Pad4)") (class "Default")
      (node (ref "CON_PROG7") (pin "4") (pinfunction "4_4") (pintype "bidirectional"))
    )
    (net (code "157") (name "unconnected-(CON_PROG7-Pad7)") (class "Default")
      (node (ref "CON_PROG7") (pin "7") (pinfunction "7_7") (pintype "bidirectional"))
    )
    (net (code "158") (name "unconnected-(CON_PROG7-Pad10)") (class "Default")
      (node (ref "CON_PROG7") (pin "10") (pinfunction "10_10") (pintype "bidirectional"))
    )
    (net (code "159") (name "unconnected-(CON_PROG7-Pad11)") (class "Default")
      (node (ref "CON_PROG7") (pin "11") (pinfunction "11_11") (pintype "bidirectional"))
    )
    (net (code "160") (name "unconnected-(CON_PROG7-Pad12)") (class "Default")
      (node (ref "CON_PROG7") (pin "12") (pinfunction "12_12") (pintype "bidirectional"))
    )
    (net (code "161") (name "unconnected-(CON_PROG7-Pad13)") (class "Default")
      (node (ref "CON_PROG7") (pin "13") (pinfunction "13_13") (pintype "bidirectional"))
    )
    (net (code "162") (name "unconnected-(CON_PROG7-Pad17)") (class "Default")
      (node (ref "CON_PROG7") (pin "17") (pinfunction "17_17") (pintype "bidirectional"))
    )
    (net (code "163") (name "unconnected-(CON_PROG7-Pad18)") (class "Default")
      (node (ref "CON_PROG7") (pin "18") (pinfunction "18_18") (pintype "bidirectional"))
    )
    (net (code "164") (name "unconnected-(CON_PROG7-Pad19)") (class "Default")
      (node (ref "CON_PROG7") (pin "19") (pinfunction "19_19") (pintype "bidirectional"))
    )
    (net (code "165") (name "unconnected-(CON_PROG7-Pad20)") (class "Default")
      (node (ref "CON_PROG7") (pin "20") (pinfunction "20_20") (pintype "bidirectional"))
    )
    (net (code "166") (name "unconnected-(CON_PROG8-Pad4)") (class "Default")
      (node (ref "CON_PROG8") (pin "4") (pinfunction "4_4") (pintype "bidirectional"))
    )
    (net (code "167") (name "unconnected-(CON_PROG8-Pad7)") (class "Default")
      (node (ref "CON_PROG8") (pin "7") (pinfunction "7_7") (pintype "bidirectional"))
    )
    (net (code "168") (name "unconnected-(CON_PROG8-Pad10)") (class "Default")
      (node (ref "CON_PROG8") (pin "10") (pinfunction "10_10") (pintype "bidirectional"))
    )
    (net (code "169") (name "unconnected-(CON_PROG8-Pad11)") (class "Default")
      (node (ref "CON_PROG8") (pin "11") (pinfunction "11_11") (pintype "bidirectional"))
    )
    (net (code "170") (name "unconnected-(CON_PROG8-Pad12)") (class "Default")
      (node (ref "CON_PROG8") (pin "12") (pinfunction "12_12") (pintype "bidirectional"))
    )
    (net (code "171") (name "unconnected-(CON_PROG8-Pad13)") (class "Default")
      (node (ref "CON_PROG8") (pin "13") (pinfunction "13_13") (pintype "bidirectional"))
    )
    (net (code "172") (name "unconnected-(CON_PROG8-Pad17)") (class "Default")
      (node (ref "CON_PROG8") (pin "17") (pinfunction "17_17") (pintype "bidirectional"))
    )
    (net (code "173") (name "unconnected-(CON_PROG8-Pad18)") (class "Default")
      (node (ref "CON_PROG8") (pin "18") (pinfunction "18_18") (pintype "bidirectional"))
    )
    (net (code "174") (name "unconnected-(CON_PROG8-Pad19)") (class "Default")
      (node (ref "CON_PROG8") (pin "19") (pinfunction "19_19") (pintype "bidirectional"))
    )
    (net (code "175") (name "unconnected-(CON_PROG8-Pad20)") (class "Default")
      (node (ref "CON_PROG8") (pin "20") (pinfunction "20_20") (pintype "bidirectional"))
    )
    (net (code "176") (name "unconnected-(CON_PROG9-Pad4)") (class "Default")
      (node (ref "CON_PROG9") (pin "4") (pinfunction "4_4") (pintype "bidirectional"))
    )
    (net (code "177") (name "unconnected-(CON_PROG9-Pad7)") (class "Default")
      (node (ref "CON_PROG9") (pin "7") (pinfunction "7_7") (pintype "bidirectional"))
    )
    (net (code "178") (name "unconnected-(CON_PROG9-Pad10)") (class "Default")
      (node (ref "CON_PROG9") (pin "10") (pinfunction "10_10") (pintype "bidirectional"))
    )
    (net (code "179") (name "unconnected-(CON_PROG9-Pad11)") (class "Default")
      (node (ref "CON_PROG9") (pin "11") (pinfunction "11_11") (pintype "bidirectional"))
    )
    (net (code "180") (name "unconnected-(CON_PROG9-Pad12)") (class "Default")
      (node (ref "CON_PROG9") (pin "12") (pinfunction "12_12") (pintype "bidirectional"))
    )
    (net (code "181") (name "unconnected-(CON_PROG9-Pad13)") (class "Default")
      (node (ref "CON_PROG9") (pin "13") (pinfunction "13_13") (pintype "bidirectional"))
    )
    (net (code "182") (name "unconnected-(CON_PROG9-Pad17)") (class "Default")
      (node (ref "CON_PROG9") (pin "17") (pinfunction "17_17") (pintype "bidirectional"))
    )
    (net (code "183") (name "unconnected-(CON_PROG9-Pad18)") (class "Default")
      (node (ref "CON_PROG9") (pin "18") (pinfunction "18_18") (pintype "bidirectional"))
    )
    (net (code "184") (name "unconnected-(CON_PROG9-Pad19)") (class "Default")
      (node (ref "CON_PROG9") (pin "19") (pinfunction "19_19") (pintype "bidirectional"))
    )
    (net (code "185") (name "unconnected-(CON_PROG9-Pad20)") (class "Default")
      (node (ref "CON_PROG9") (pin "20") (pinfunction "20_20") (pintype "bidirectional"))
    )
    (net (code "186") (name "unconnected-(IC100-AREF-Pad21)") (class "Default")
      (node (ref "IC100") (pin "21") (pinfunction "AREF_21") (pintype "passive"))
    )
    (net (code "187") (name "unconnected-(IC100-PB0(ICP)-Pad14)") (class "Default")
      (node (ref "IC100") (pin "14") (pinfunction "PB0(ICP)_14") (pintype "bidirectional"))
    )
    (net (code "188") (name "unconnected-(IC100-PB1(OC1A)-Pad15)") (class "Default")
      (node (ref "IC100") (pin "15") (pinfunction "PB1(OC1A)_15") (pintype "bidirectional"))
    )
    (net (code "189") (name "unconnected-(IC100-PB2(SS{slash}OC1B)-Pad16)") (class "Default")
      (node (ref "IC100") (pin "16") (pinfunction "PB2(SS/OC1B)_16") (pintype "bidirectional"))
    )
    (net (code "190") (name "unconnected-(IC100-PB6(XTAL1{slash}TOSC1)-Pad9)") (class "Default")
      (node (ref "IC100") (pin "9") (pinfunction "PB6(XTAL1/TOSC1)_9") (pintype "bidirectional"))
    )
    (net (code "191") (name "unconnected-(IC100-PB7(XTAL2{slash}TOSC2)-Pad10)") (class "Default")
      (node (ref "IC100") (pin "10") (pinfunction "PB7(XTAL2/TOSC2)_10") (pintype "bidirectional"))
    )
    (net (code "192") (name "unconnected-(ISP-Pad3)") (class "Default")
      (node (ref "ISP") (pin "3") (pinfunction "3_3") (pintype "passive"))
    )
    (net (code "193") (name "unconnected-(LCD-Pad7)") (class "Default")
      (node (ref "LCD") (pin "7") (pinfunction "7_7") (pintype "passive"))
    )
    (net (code "194") (name "unconnected-(LCD-Pad8)") (class "Default")
      (node (ref "LCD") (pin "8") (pinfunction "8_8") (pintype "passive"))
    )
    (net (code "195") (name "unconnected-(LCD-Pad9)") (class "Default")
      (node (ref "LCD") (pin "9") (pinfunction "9_9") (pintype "passive"))
    )
    (net (code "196") (name "unconnected-(LCD-Pad10)") (class "Default")
      (node (ref "LCD") (pin "10") (pinfunction "10_10") (pintype "passive"))
    )
  )
)
